# LinTempCont_4ch_proto.net
KiCad netlist of a schematic drawn in EAGLE
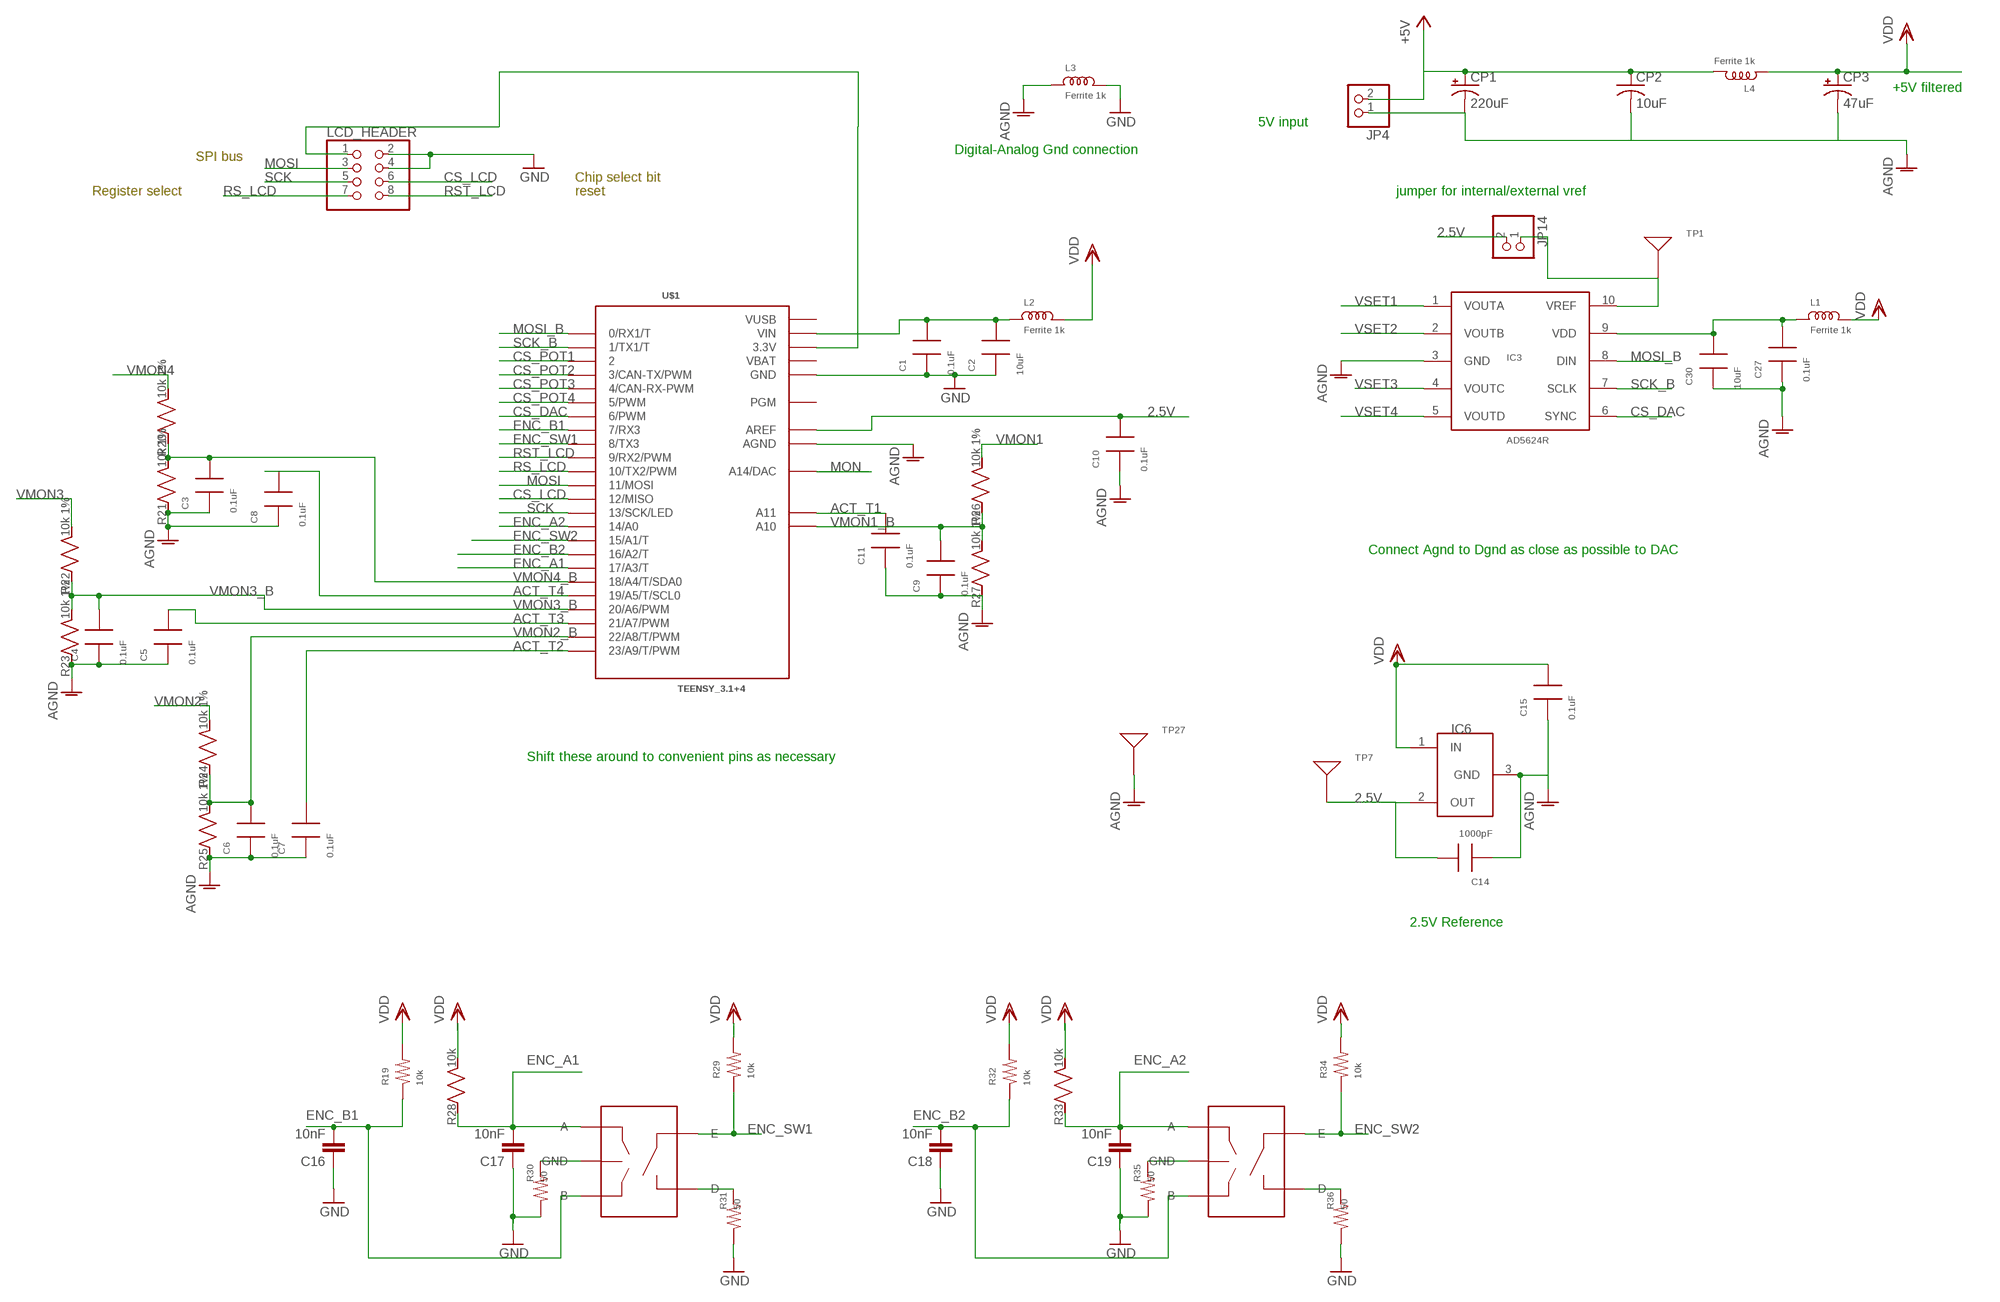
[diagram p0: schematic, sheet 1]
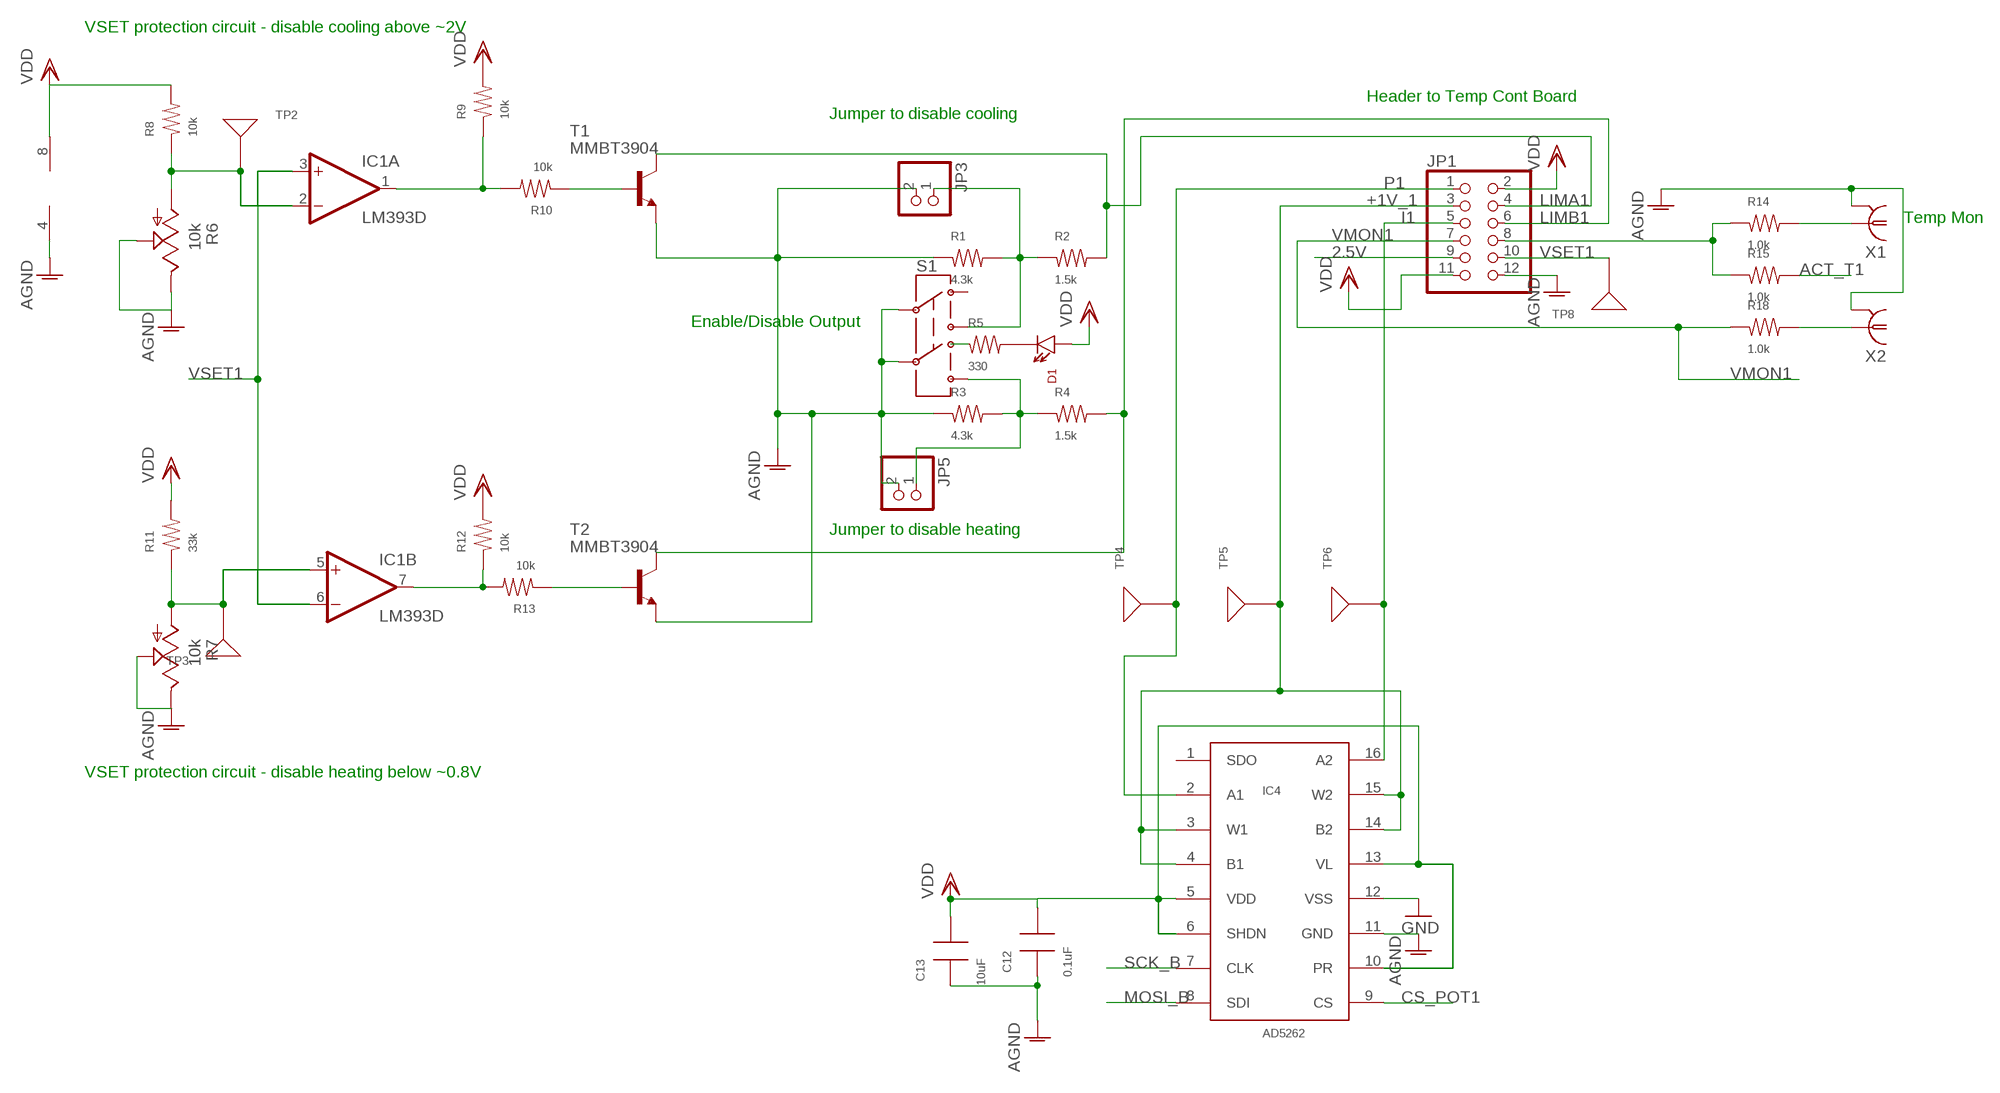
[diagram p1: schematic, sheet 2]
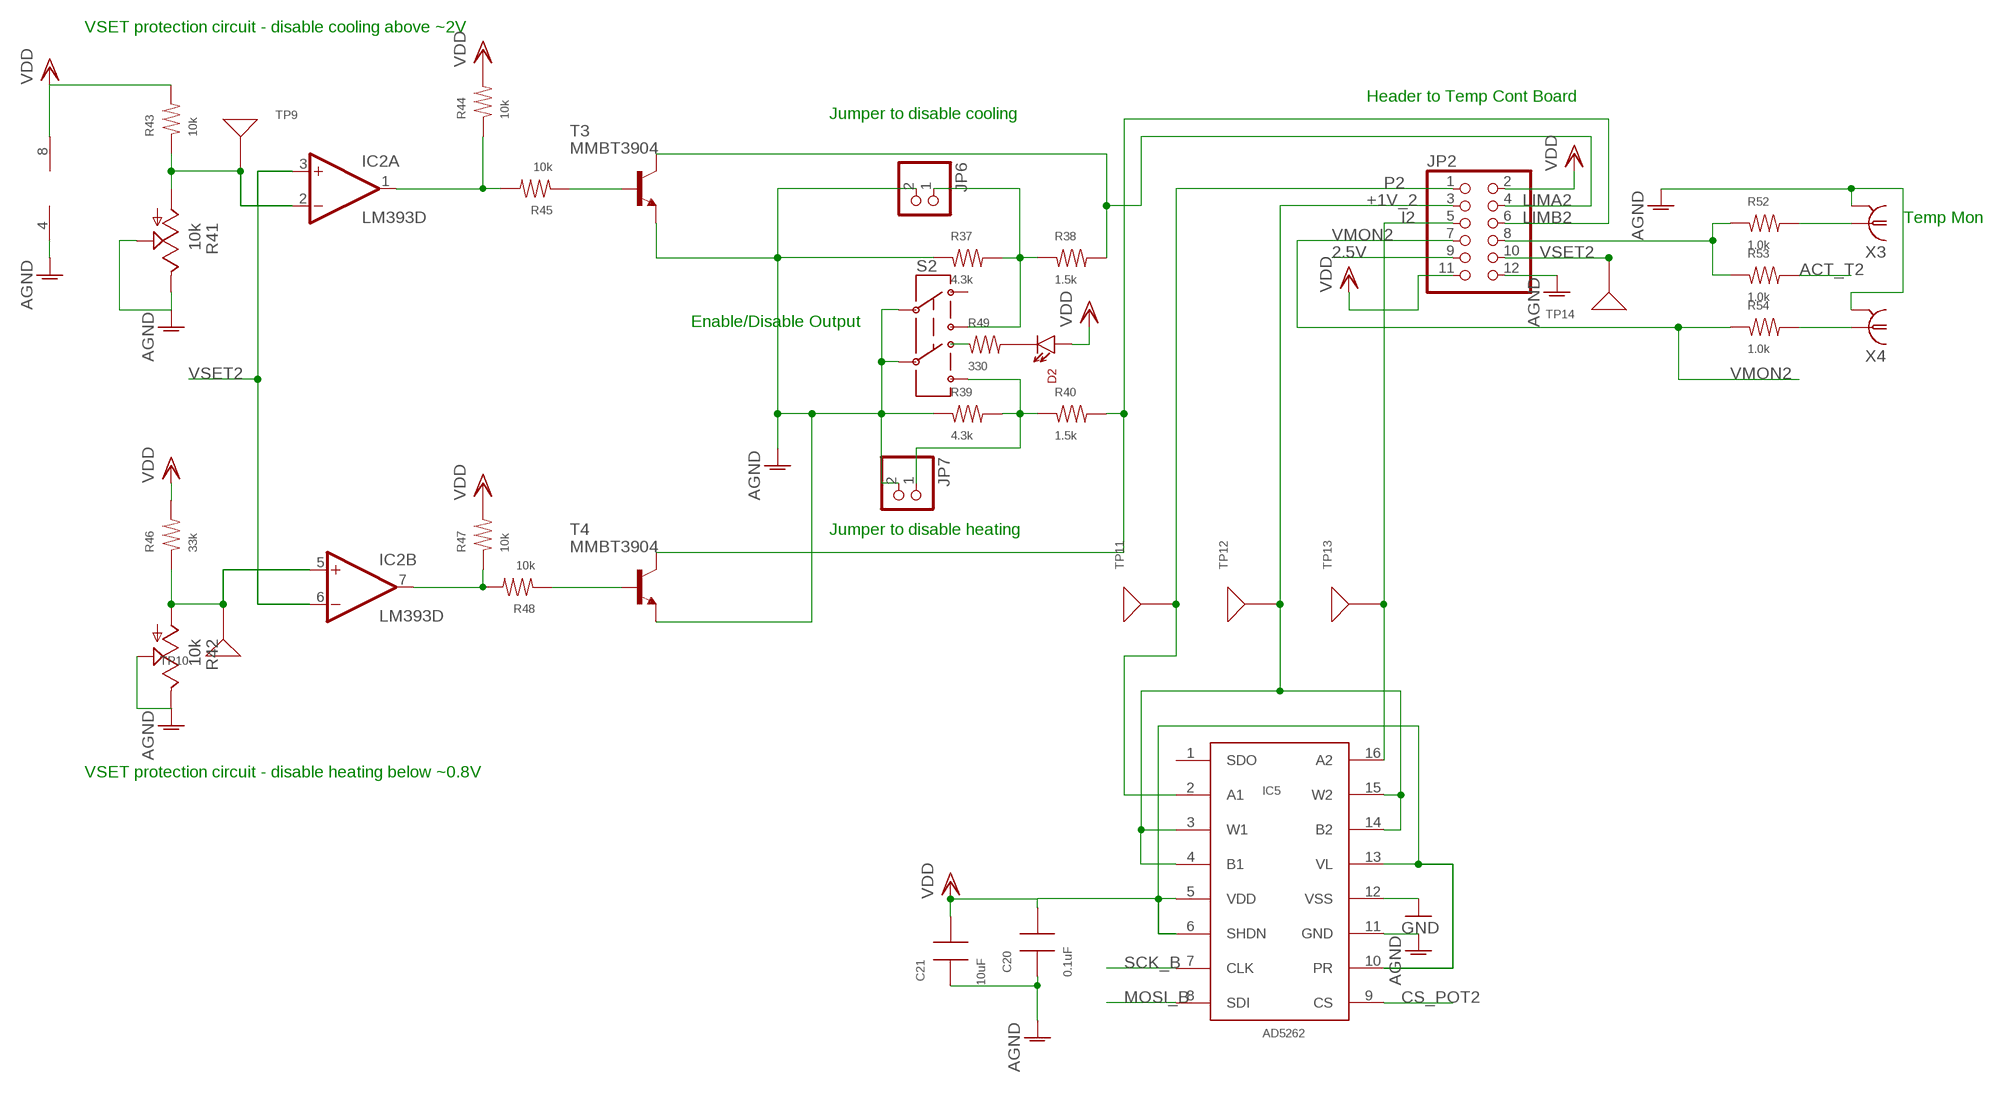
[diagram p2: schematic, sheet 3]
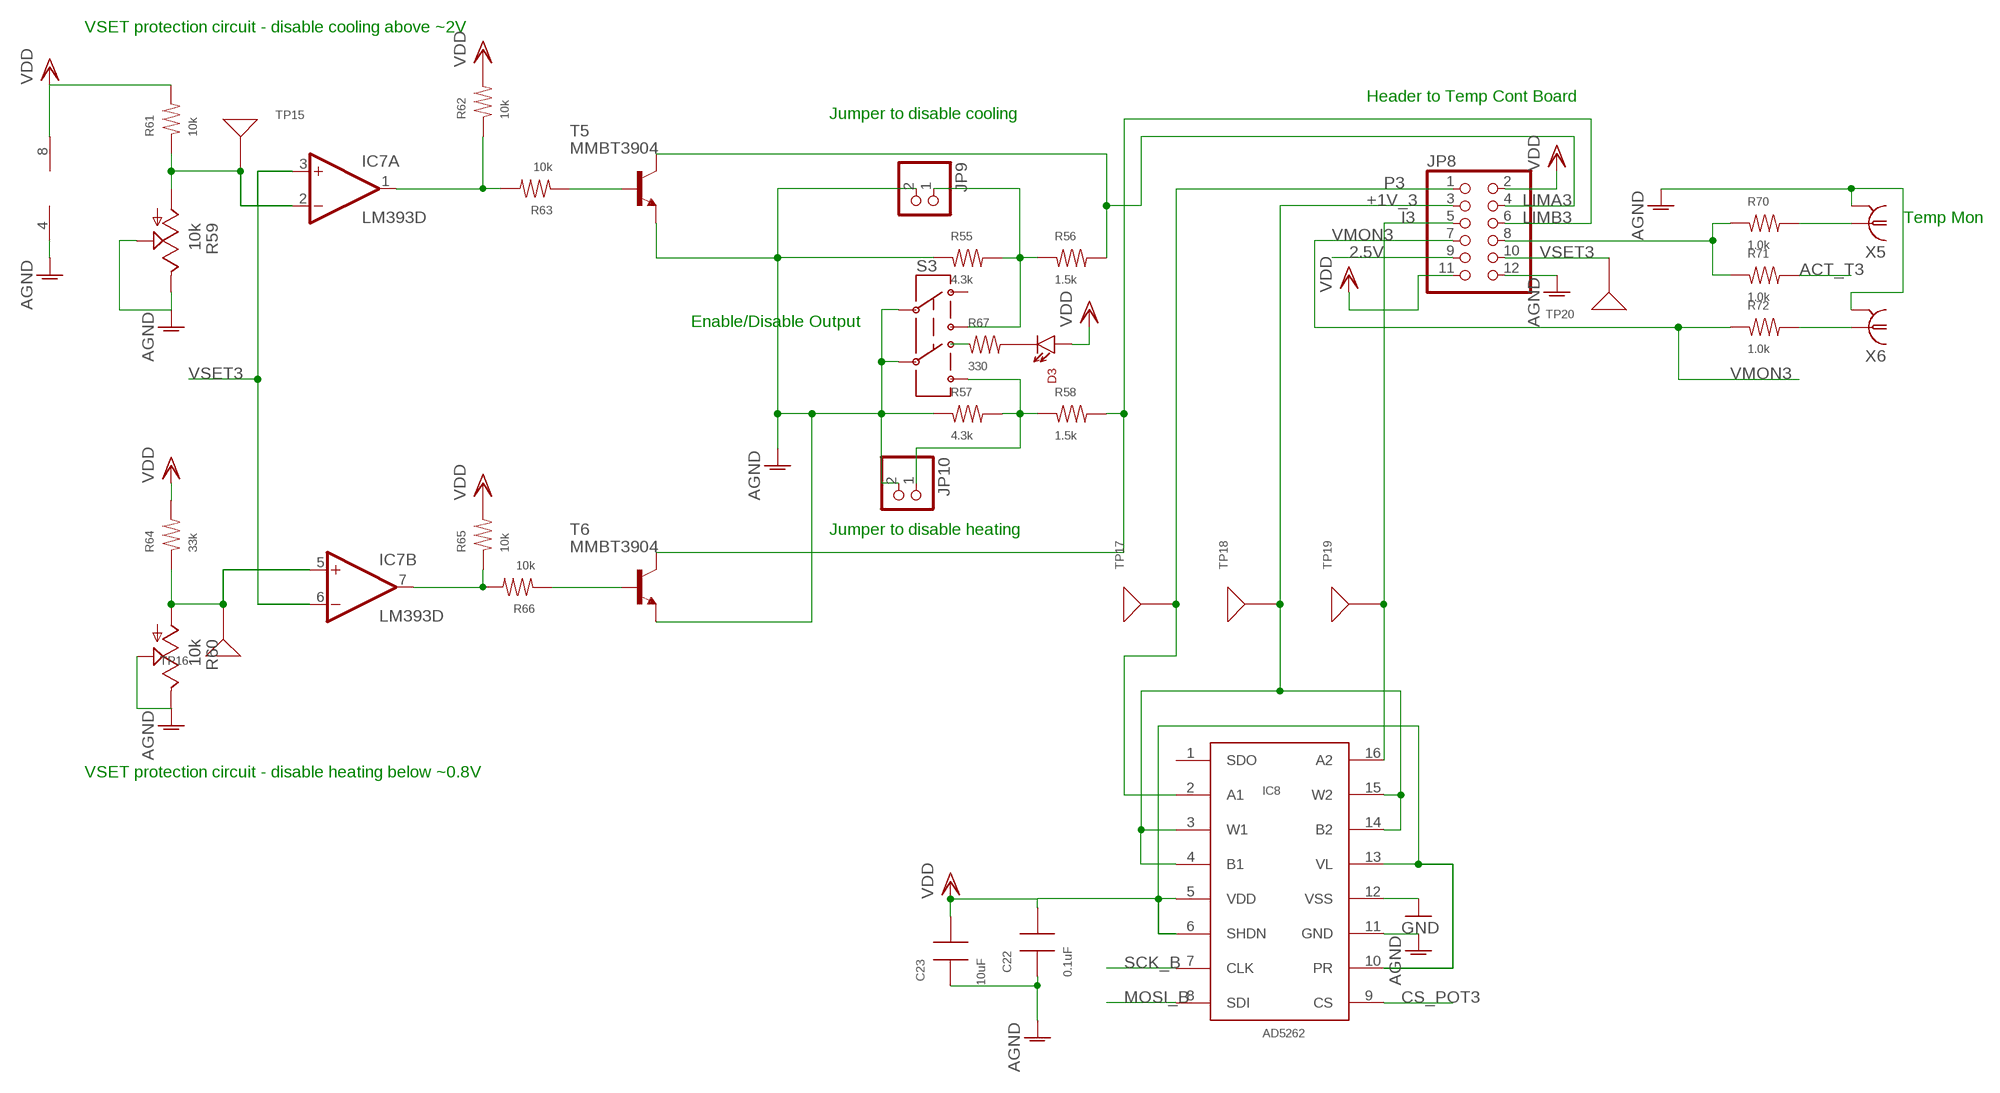
[diagram p3: schematic, sheet 4]
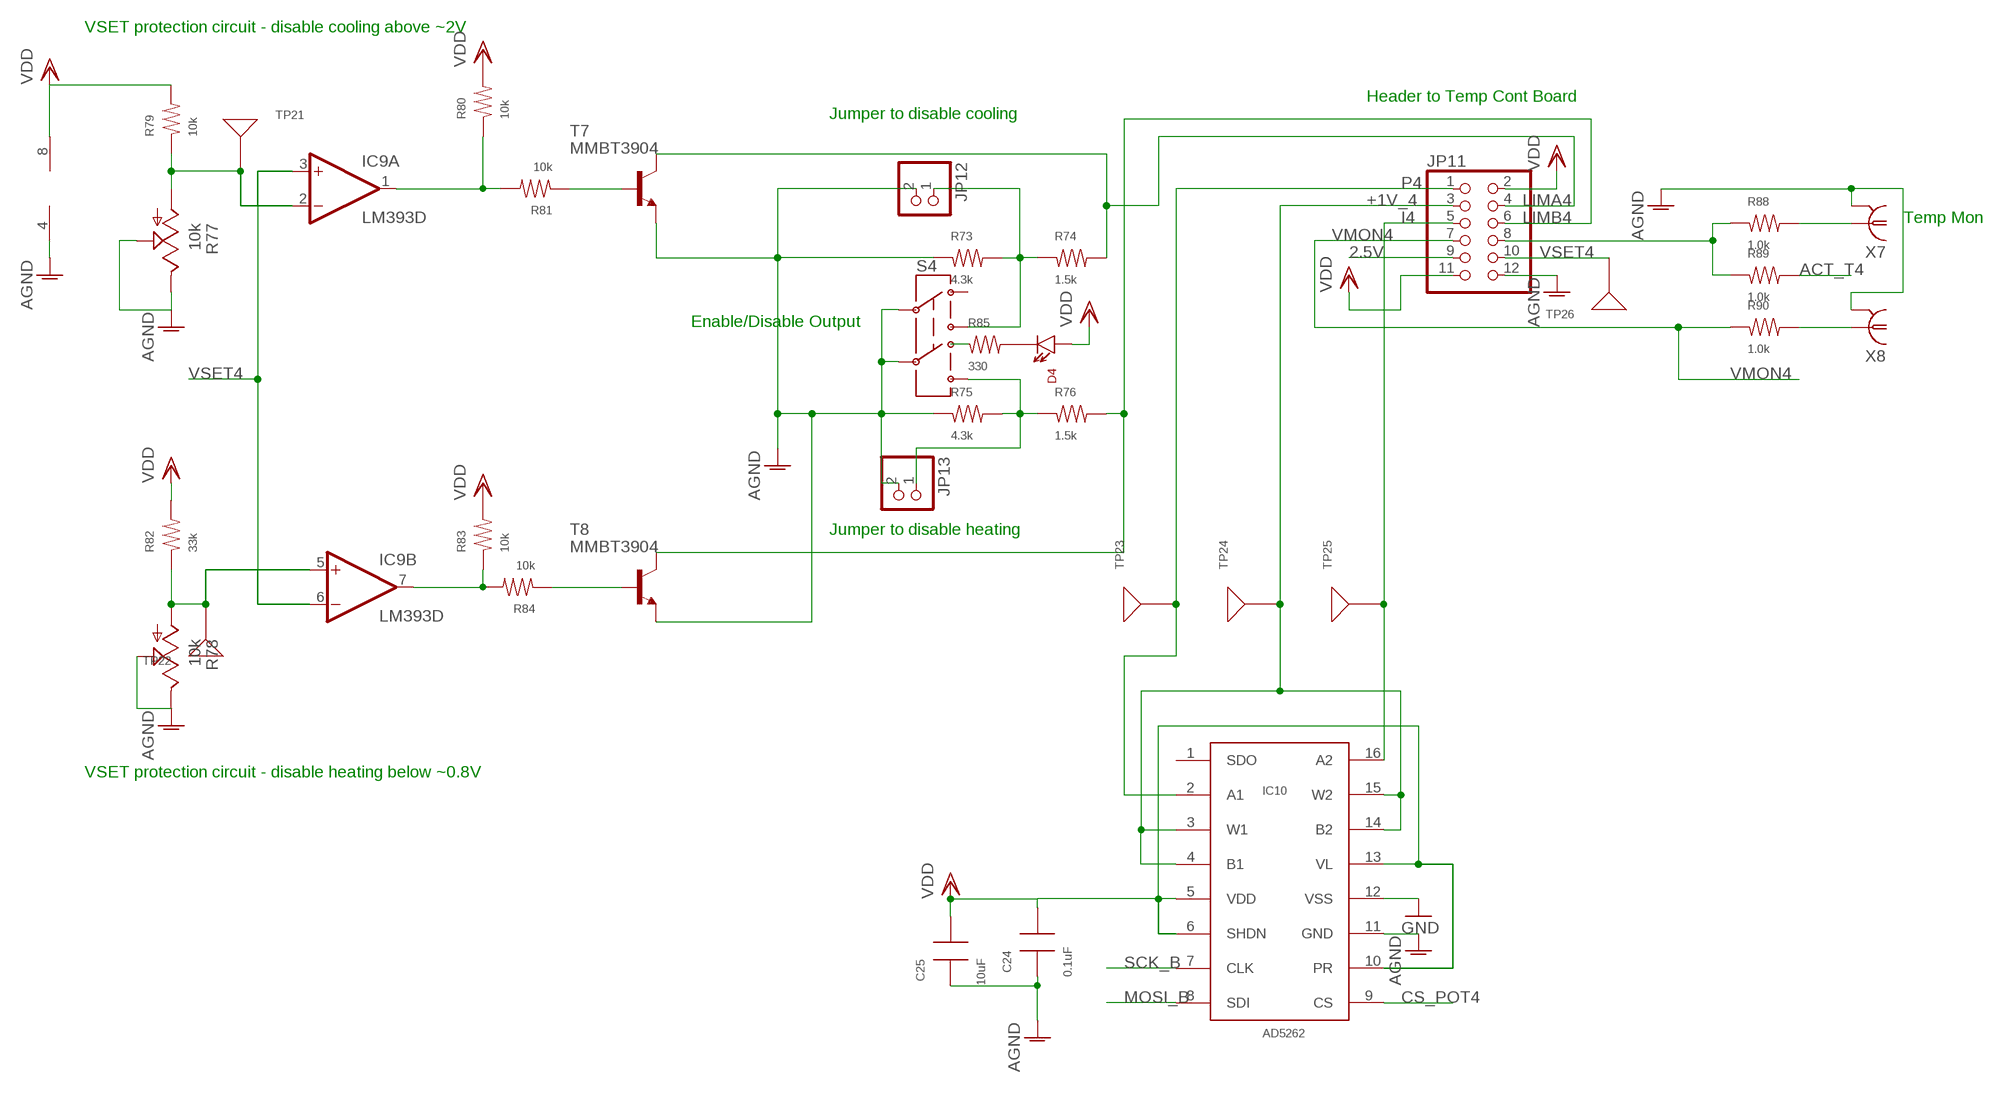
[diagram p4: schematic, sheet 5]

(export (version "E")
  (design (tool "Eeschema 10.0.6"))
  (components
    (comp (ref "C24")
      (value "0.1uF")
      (footprint "eagle-import:0603")
      (libsource (lib "eagle-import") (part "CAP0603"))
    )
    (comp (ref "C25")
      (value "10uF")
      (footprint "eagle-import:0805")
      (libsource (lib "eagle-import") (part "CAP0805"))
    )
    (comp (ref "D4")
      (value "LED/MINI-IND")
      (footprint "eagle-import:HLMP--F0010")
      (libsource (lib "eagle-import") (part "LED/MINI-IND"))
    )
    (comp (ref "IC9")
      (value "LM393D")
      (footprint "eagle-import:SO08")
      (libsource (lib "eagle-import") (part "LM393D"))
    )
    (comp (ref "IC10")
      (value "AD5262")
      (footprint "eagle-import:TSSOP16")
      (libsource (lib "eagle-import") (part "AD5262"))
    )
    (comp (ref "JP11")
      (value "PINHD-2X6/90")
      (footprint "eagle-import:2X06_90")
      (libsource (lib "eagle-import") (part "PINHD-2X6/90"))
    )
    (comp (ref "JP12")
      (value "PINHD-1X2")
      (footprint "eagle-import:1X02")
      (libsource (lib "eagle-import") (part "PINHD-1X2"))
    )
    (comp (ref "JP13")
      (value "PINHD-1X2")
      (footprint "eagle-import:1X02")
      (libsource (lib "eagle-import") (part "PINHD-1X2"))
    )
    (comp (ref "R73")
      (value "4.3k")
      (footprint "eagle-import:0603")
      (libsource (lib "eagle-import") (part "RES0603"))
    )
    (comp (ref "R74")
      (value "1.5k")
      (footprint "eagle-import:0603")
      (libsource (lib "eagle-import") (part "RES0603"))
    )
    (comp (ref "R75")
      (value "4.3k")
      (footprint "eagle-import:0603")
      (libsource (lib "eagle-import") (part "RES0603"))
    )
    (comp (ref "R76")
      (value "1.5k")
      (footprint "eagle-import:0603")
      (libsource (lib "eagle-import") (part "RES0603"))
    )
    (comp (ref "R77")
      (value "10k")
      (footprint "eagle-import:64WPOT")
      (libsource (lib "eagle-import") (part "MODEL64_TRIMPOT/TOP-ADJ"))
    )
    (comp (ref "R78")
      (value "10k")
      (footprint "eagle-import:64WPOT")
      (libsource (lib "eagle-import") (part "MODEL64_TRIMPOT/TOP-ADJ"))
    )
    (comp (ref "R79")
      (value "10k")
      (footprint "eagle-import:0603")
      (libsource (lib "eagle-import") (part "RES0603"))
    )
    (comp (ref "R80")
      (value "10k")
      (footprint "eagle-import:0603")
      (libsource (lib "eagle-import") (part "RES0603"))
    )
    (comp (ref "R81")
      (value "10k")
      (footprint "eagle-import:0603")
      (libsource (lib "eagle-import") (part "RES0603"))
    )
    (comp (ref "R82")
      (value "33k")
      (footprint "eagle-import:0603")
      (libsource (lib "eagle-import") (part "RES0603"))
    )
    (comp (ref "R83")
      (value "10k")
      (footprint "eagle-import:0603")
      (libsource (lib "eagle-import") (part "RES0603"))
    )
    (comp (ref "R84")
      (value "10k")
      (footprint "eagle-import:0603")
      (libsource (lib "eagle-import") (part "RES0603"))
    )
    (comp (ref "R85")
      (value "330")
      (footprint "eagle-import:0603")
      (libsource (lib "eagle-import") (part "RES0603"))
    )
    (comp (ref "R88")
      (value "1.0k")
      (footprint "eagle-import:0603")
      (libsource (lib "eagle-import") (part "RES0603"))
    )
    (comp (ref "R89")
      (value "1.0k")
      (footprint "eagle-import:0603")
      (libsource (lib "eagle-import") (part "RES0603"))
    )
    (comp (ref "R90")
      (value "1.0k")
      (footprint "eagle-import:0603")
      (libsource (lib "eagle-import") (part "RES0603"))
    )
    (comp (ref "S4")
      (value "SWITCH-DPDT/VER")
      (footprint "eagle-import:E-SWITCH-100-M7")
      (libsource (lib "eagle-import") (part "SWITCH-DPDT/VER"))
    )
    (comp (ref "T7")
      (value "MMBT3904")
      (footprint "eagle-import:SOT-23")
      (libsource (lib "eagle-import") (part "MMBT3904"))
    )
    (comp (ref "T8")
      (value "MMBT3904")
      (footprint "eagle-import:SOT-23")
      (libsource (lib "eagle-import") (part "MMBT3904"))
    )
    (comp (ref "TP21")
      (value "TESTPT")
      (footprint "eagle-import:1206TESTPAD")
      (libsource (lib "eagle-import") (part "TESTPT"))
    )
    (comp (ref "TP22")
      (value "TESTPT")
      (footprint "eagle-import:1206TESTPAD")
      (libsource (lib "eagle-import") (part "TESTPT"))
    )
    (comp (ref "TP23")
      (value "TESTPT")
      (footprint "eagle-import:1206TESTPAD")
      (libsource (lib "eagle-import") (part "TESTPT"))
    )
    (comp (ref "TP24")
      (value "TESTPT")
      (footprint "eagle-import:1206TESTPAD")
      (libsource (lib "eagle-import") (part "TESTPT"))
    )
    (comp (ref "TP25")
      (value "TESTPT")
      (footprint "eagle-import:1206TESTPAD")
      (libsource (lib "eagle-import") (part "TESTPT"))
    )
    (comp (ref "TP26")
      (value "TESTPT")
      (footprint "eagle-import:1206TESTPAD")
      (libsource (lib "eagle-import") (part "TESTPT"))
    )
    (comp (ref "X7")
      (value "BNC-H")
      (footprint "eagle-import:BNC90")
      (libsource (lib "eagle-import") (part "BNC-H"))
    )
    (comp (ref "X8")
      (value "BNC-H")
      (footprint "eagle-import:BNC90")
      (libsource (lib "eagle-import") (part "BNC-H"))
    )
    (comp (ref "C20")
      (value "0.1uF")
      (footprint "eagle-import:0603")
      (libsource (lib "eagle-import") (part "CAP0603"))
    )
    (comp (ref "C21")
      (value "10uF")
      (footprint "eagle-import:0805")
      (libsource (lib "eagle-import") (part "CAP0805"))
    )
    (comp (ref "D2")
      (value "LED/MINI-IND")
      (footprint "eagle-import:HLMP--F0010")
      (libsource (lib "eagle-import") (part "LED/MINI-IND"))
    )
    (comp (ref "IC2")
      (value "LM393D")
      (footprint "eagle-import:SO08")
      (libsource (lib "eagle-import") (part "LM393D"))
    )
    (comp (ref "IC5")
      (value "AD5262")
      (footprint "eagle-import:TSSOP16")
      (libsource (lib "eagle-import") (part "AD5262"))
    )
    (comp (ref "JP2")
      (value "PINHD-2X6/90")
      (footprint "eagle-import:2X06_90")
      (libsource (lib "eagle-import") (part "PINHD-2X6/90"))
    )
    (comp (ref "JP6")
      (value "PINHD-1X2")
      (footprint "eagle-import:1X02")
      (libsource (lib "eagle-import") (part "PINHD-1X2"))
    )
    (comp (ref "JP7")
      (value "PINHD-1X2")
      (footprint "eagle-import:1X02")
      (libsource (lib "eagle-import") (part "PINHD-1X2"))
    )
    (comp (ref "R37")
      (value "4.3k")
      (footprint "eagle-import:0603")
      (libsource (lib "eagle-import") (part "RES0603"))
    )
    (comp (ref "R38")
      (value "1.5k")
      (footprint "eagle-import:0603")
      (libsource (lib "eagle-import") (part "RES0603"))
    )
    (comp (ref "R39")
      (value "4.3k")
      (footprint "eagle-import:0603")
      (libsource (lib "eagle-import") (part "RES0603"))
    )
    (comp (ref "R40")
      (value "1.5k")
      (footprint "eagle-import:0603")
      (libsource (lib "eagle-import") (part "RES0603"))
    )
    (comp (ref "R41")
      (value "10k")
      (footprint "eagle-import:64WPOT")
      (libsource (lib "eagle-import") (part "MODEL64_TRIMPOT/TOP-ADJ"))
    )
    (comp (ref "R42")
      (value "10k")
      (footprint "eagle-import:64WPOT")
      (libsource (lib "eagle-import") (part "MODEL64_TRIMPOT/TOP-ADJ"))
    )
    (comp (ref "R43")
      (value "10k")
      (footprint "eagle-import:0603")
      (libsource (lib "eagle-import") (part "RES0603"))
    )
    (comp (ref "R44")
      (value "10k")
      (footprint "eagle-import:0603")
      (libsource (lib "eagle-import") (part "RES0603"))
    )
    (comp (ref "R45")
      (value "10k")
      (footprint "eagle-import:0603")
      (libsource (lib "eagle-import") (part "RES0603"))
    )
    (comp (ref "R46")
      (value "33k")
      (footprint "eagle-import:0603")
      (libsource (lib "eagle-import") (part "RES0603"))
    )
    (comp (ref "R47")
      (value "10k")
      (footprint "eagle-import:0603")
      (libsource (lib "eagle-import") (part "RES0603"))
    )
    (comp (ref "R48")
      (value "10k")
      (footprint "eagle-import:0603")
      (libsource (lib "eagle-import") (part "RES0603"))
    )
    (comp (ref "R49")
      (value "330")
      (footprint "eagle-import:0603")
      (libsource (lib "eagle-import") (part "RES0603"))
    )
    (comp (ref "R52")
      (value "1.0k")
      (footprint "eagle-import:0603")
      (libsource (lib "eagle-import") (part "RES0603"))
    )
    (comp (ref "R53")
      (value "1.0k")
      (footprint "eagle-import:0603")
      (libsource (lib "eagle-import") (part "RES0603"))
    )
    (comp (ref "R54")
      (value "1.0k")
      (footprint "eagle-import:0603")
      (libsource (lib "eagle-import") (part "RES0603"))
    )
    (comp (ref "S2")
      (value "SWITCH-DPDT/VER")
      (footprint "eagle-import:E-SWITCH-100-M7")
      (libsource (lib "eagle-import") (part "SWITCH-DPDT/VER"))
    )
    (comp (ref "T3")
      (value "MMBT3904")
      (footprint "eagle-import:SOT-23")
      (libsource (lib "eagle-import") (part "MMBT3904"))
    )
    (comp (ref "T4")
      (value "MMBT3904")
      (footprint "eagle-import:SOT-23")
      (libsource (lib "eagle-import") (part "MMBT3904"))
    )
    (comp (ref "TP9")
      (value "TESTPT")
      (footprint "eagle-import:1206TESTPAD")
      (libsource (lib "eagle-import") (part "TESTPT"))
    )
    (comp (ref "TP10")
      (value "TESTPT")
      (footprint "eagle-import:1206TESTPAD")
      (libsource (lib "eagle-import") (part "TESTPT"))
    )
    (comp (ref "TP11")
      (value "TESTPT")
      (footprint "eagle-import:1206TESTPAD")
      (libsource (lib "eagle-import") (part "TESTPT"))
    )
    (comp (ref "TP12")
      (value "TESTPT")
      (footprint "eagle-import:1206TESTPAD")
      (libsource (lib "eagle-import") (part "TESTPT"))
    )
    (comp (ref "TP13")
      (value "TESTPT")
      (footprint "eagle-import:1206TESTPAD")
      (libsource (lib "eagle-import") (part "TESTPT"))
    )
    (comp (ref "TP14")
      (value "TESTPT")
      (footprint "eagle-import:1206TESTPAD")
      (libsource (lib "eagle-import") (part "TESTPT"))
    )
    (comp (ref "X3")
      (value "BNC-H")
      (footprint "eagle-import:BNC90")
      (libsource (lib "eagle-import") (part "BNC-H"))
    )
    (comp (ref "X4")
      (value "BNC-H")
      (footprint "eagle-import:BNC90")
      (libsource (lib "eagle-import") (part "BNC-H"))
    )
    (comp (ref "C12")
      (value "0.1uF")
      (footprint "eagle-import:0603")
      (libsource (lib "eagle-import") (part "CAP0603"))
    )
    (comp (ref "C13")
      (value "10uF")
      (footprint "eagle-import:0805")
      (libsource (lib "eagle-import") (part "CAP0805"))
    )
    (comp (ref "D1")
      (value "LED/MINI-IND")
      (footprint "eagle-import:HLMP--F0010")
      (libsource (lib "eagle-import") (part "LED/MINI-IND"))
    )
    (comp (ref "IC1")
      (value "LM393D")
      (footprint "eagle-import:SO08")
      (libsource (lib "eagle-import") (part "LM393D"))
    )
    (comp (ref "IC4")
      (value "AD5262")
      (footprint "eagle-import:TSSOP16")
      (libsource (lib "eagle-import") (part "AD5262"))
    )
    (comp (ref "JP1")
      (value "PINHD-2X6/90")
      (footprint "eagle-import:2X06_90")
      (libsource (lib "eagle-import") (part "PINHD-2X6/90"))
    )
    (comp (ref "JP3")
      (value "PINHD-1X2")
      (footprint "eagle-import:1X02")
      (libsource (lib "eagle-import") (part "PINHD-1X2"))
    )
    (comp (ref "JP5")
      (value "PINHD-1X2")
      (footprint "eagle-import:1X02")
      (libsource (lib "eagle-import") (part "PINHD-1X2"))
    )
    (comp (ref "R1")
      (value "4.3k")
      (footprint "eagle-import:0603")
      (libsource (lib "eagle-import") (part "RES0603"))
    )
    (comp (ref "R2")
      (value "1.5k")
      (footprint "eagle-import:0603")
      (libsource (lib "eagle-import") (part "RES0603"))
    )
    (comp (ref "R3")
      (value "4.3k")
      (footprint "eagle-import:0603")
      (libsource (lib "eagle-import") (part "RES0603"))
    )
    (comp (ref "R4")
      (value "1.5k")
      (footprint "eagle-import:0603")
      (libsource (lib "eagle-import") (part "RES0603"))
    )
    (comp (ref "R5")
      (value "330")
      (footprint "eagle-import:0603")
      (libsource (lib "eagle-import") (part "RES0603"))
    )
    (comp (ref "R6")
      (value "10k")
      (footprint "eagle-import:64WPOT")
      (libsource (lib "eagle-import") (part "MODEL64_TRIMPOT/TOP-ADJ"))
    )
    (comp (ref "R7")
      (value "10k")
      (footprint "eagle-import:64WPOT")
      (libsource (lib "eagle-import") (part "MODEL64_TRIMPOT/TOP-ADJ"))
    )
    (comp (ref "R8")
      (value "10k")
      (footprint "eagle-import:0603")
      (libsource (lib "eagle-import") (part "RES0603"))
    )
    (comp (ref "R9")
      (value "10k")
      (footprint "eagle-import:0603")
      (libsource (lib "eagle-import") (part "RES0603"))
    )
    (comp (ref "R10")
      (value "10k")
      (footprint "eagle-import:0603")
      (libsource (lib "eagle-import") (part "RES0603"))
    )
    (comp (ref "R11")
      (value "33k")
      (footprint "eagle-import:0603")
      (libsource (lib "eagle-import") (part "RES0603"))
    )
    (comp (ref "R12")
      (value "10k")
      (footprint "eagle-import:0603")
      (libsource (lib "eagle-import") (part "RES0603"))
    )
    (comp (ref "R13")
      (value "10k")
      (footprint "eagle-import:0603")
      (libsource (lib "eagle-import") (part "RES0603"))
    )
    (comp (ref "R14")
      (value "1.0k")
      (footprint "eagle-import:0603")
      (libsource (lib "eagle-import") (part "RES0603"))
    )
    (comp (ref "R15")
      (value "1.0k")
      (footprint "eagle-import:0603")
      (libsource (lib "eagle-import") (part "RES0603"))
    )
    (comp (ref "R18")
      (value "1.0k")
      (footprint "eagle-import:0603")
      (libsource (lib "eagle-import") (part "RES0603"))
    )
    (comp (ref "S1")
      (value "SWITCH-DPDT/VER")
      (footprint "eagle-import:E-SWITCH-100-M7")
      (libsource (lib "eagle-import") (part "SWITCH-DPDT/VER"))
    )
    (comp (ref "T1")
      (value "MMBT3904")
      (footprint "eagle-import:SOT-23")
      (libsource (lib "eagle-import") (part "MMBT3904"))
    )
    (comp (ref "T2")
      (value "MMBT3904")
      (footprint "eagle-import:SOT-23")
      (libsource (lib "eagle-import") (part "MMBT3904"))
    )
    (comp (ref "TP2")
      (value "TESTPT")
      (footprint "eagle-import:1206TESTPAD")
      (libsource (lib "eagle-import") (part "TESTPT"))
    )
    (comp (ref "TP3")
      (value "TESTPT")
      (footprint "eagle-import:1206TESTPAD")
      (libsource (lib "eagle-import") (part "TESTPT"))
    )
    (comp (ref "TP4")
      (value "TESTPT")
      (footprint "eagle-import:1206TESTPAD")
      (libsource (lib "eagle-import") (part "TESTPT"))
    )
    (comp (ref "TP5")
      (value "TESTPT")
      (footprint "eagle-import:1206TESTPAD")
      (libsource (lib "eagle-import") (part "TESTPT"))
    )
    (comp (ref "TP6")
      (value "TESTPT")
      (footprint "eagle-import:1206TESTPAD")
      (libsource (lib "eagle-import") (part "TESTPT"))
    )
    (comp (ref "TP8")
      (value "TESTPT")
      (footprint "eagle-import:1206TESTPAD")
      (libsource (lib "eagle-import") (part "TESTPT"))
    )
    (comp (ref "X1")
      (value "BNC-H")
      (footprint "eagle-import:BNC90")
      (libsource (lib "eagle-import") (part "BNC-H"))
    )
    (comp (ref "X2")
      (value "BNC-H")
      (footprint "eagle-import:BNC90")
      (libsource (lib "eagle-import") (part "BNC-H"))
    )
    (comp (ref "C1")
      (value "0.1uF")
      (footprint "eagle-import:0603")
      (libsource (lib "eagle-import") (part "CAP0603"))
    )
    (comp (ref "C2")
      (value "10uF")
      (footprint "eagle-import:0805")
      (libsource (lib "eagle-import") (part "CAP0805"))
    )
    (comp (ref "C3")
      (value "0.1uF")
      (footprint "eagle-import:0603")
      (libsource (lib "eagle-import") (part "CAP0603"))
    )
    (comp (ref "C4")
      (value "0.1uF")
      (footprint "eagle-import:0603")
      (libsource (lib "eagle-import") (part "CAP0603"))
    )
    (comp (ref "C5")
      (value "0.1uF")
      (footprint "eagle-import:0603")
      (libsource (lib "eagle-import") (part "CAP0603"))
    )
    (comp (ref "C6")
      (value "0.1uF")
      (footprint "eagle-import:0603")
      (libsource (lib "eagle-import") (part "CAP0603"))
    )
    (comp (ref "C7")
      (value "0.1uF")
      (footprint "eagle-import:0603")
      (libsource (lib "eagle-import") (part "CAP0603"))
    )
    (comp (ref "C8")
      (value "0.1uF")
      (footprint "eagle-import:0603")
      (libsource (lib "eagle-import") (part "CAP0603"))
    )
    (comp (ref "C9")
      (value "0.1uF")
      (footprint "eagle-import:0603")
      (libsource (lib "eagle-import") (part "CAP0603"))
    )
    (comp (ref "C10")
      (value "0.1uF")
      (footprint "eagle-import:0603")
      (libsource (lib "eagle-import") (part "CAP0603"))
    )
    (comp (ref "C11")
      (value "0.1uF")
      (footprint "eagle-import:0603")
      (libsource (lib "eagle-import") (part "CAP0603"))
    )
    (comp (ref "C14")
      (value "1000pF")
      (footprint "eagle-import:0603")
      (libsource (lib "eagle-import") (part "CAP0603"))
    )
    (comp (ref "C15")
      (value "0.1uF")
      (footprint "eagle-import:0603")
      (libsource (lib "eagle-import") (part "CAP0603"))
    )
    (comp (ref "C16")
      (value "10nF")
      (footprint "eagle-import:C0603")
      (libsource (lib "eagle-import") (part "C-EUC0603"))
    )
    (comp (ref "C17")
      (value "10nF")
      (footprint "eagle-import:C0603")
      (libsource (lib "eagle-import") (part "C-EUC0603"))
    )
    (comp (ref "C18")
      (value "10nF")
      (footprint "eagle-import:C0603")
      (libsource (lib "eagle-import") (part "C-EUC0603"))
    )
    (comp (ref "C19")
      (value "10nF")
      (footprint "eagle-import:C0603")
      (libsource (lib "eagle-import") (part "C-EUC0603"))
    )
    (comp (ref "C27")
      (value "0.1uF")
      (footprint "eagle-import:0603")
      (libsource (lib "eagle-import") (part "CAP0603"))
    )
    (comp (ref "C30")
      (value "10uF")
      (footprint "eagle-import:0805")
      (libsource (lib "eagle-import") (part "CAP0805"))
    )
    (comp (ref "CP1")
      (value "220uF")
      (footprint "eagle-import:PANASONIC_F")
      (libsource (lib "eagle-import") (part "CPOL-USF"))
    )
    (comp (ref "CP2")
      (value "10uF")
      (footprint "eagle-import:C0805K")
      (libsource (lib "eagle-import") (part "C-USC0805K"))
    )
    (comp (ref "CP3")
      (value "47uF")
      (footprint "eagle-import:CT7343")
      (libsource (lib "eagle-import") (part "CPOL-USCT7343"))
    )
    (comp (ref "ENC1")
      (value "PEC09")
      (footprint "eagle-import:PEC092320FS")
      (libsource (lib "eagle-import") (part "PEC09"))
    )
    (comp (ref "ENC2")
      (value "PEC09")
      (footprint "eagle-import:PEC092320FS")
      (libsource (lib "eagle-import") (part "PEC09"))
    )
    (comp (ref "IC3")
      (value "AD5624R")
      (footprint "eagle-import:MSOP10")
      (libsource (lib "eagle-import") (part "AD5624R"))
    )
    (comp (ref "IC6")
      (value "TS6001")
      (footprint "eagle-import:SOT-23")
      (libsource (lib "eagle-import") (part "TS6001"))
    )
    (comp (ref "JP4")
      (value "SCRWTRM-1X2")
      (footprint "eagle-import:1X02_SCRWTRM")
      (libsource (lib "eagle-import") (part "SCRWTRM-1X2"))
    )
    (comp (ref "JP14")
      (value "PINHD-1X2")
      (footprint "eagle-import:1X02")
      (libsource (lib "eagle-import") (part "PINHD-1X2"))
    )
    (comp (ref "L1")
      (value "Ferrite 1k")
      (footprint "eagle-import:0805")
      (libsource (lib "eagle-import") (part "INDUCTOR-0805"))
    )
    (comp (ref "L2")
      (value "Ferrite 1k")
      (footprint "eagle-import:0805")
      (libsource (lib "eagle-import") (part "INDUCTOR-0805"))
    )
    (comp (ref "L3")
      (value "Ferrite 1k")
      (footprint "eagle-import:0805")
      (libsource (lib "eagle-import") (part "INDUCTOR-0805"))
    )
    (comp (ref "L4")
      (value "Ferrite 1k")
      (footprint "eagle-import:0805")
      (libsource (lib "eagle-import") (part "INDUCTOR-0805"))
    )
    (comp (ref "LCD_HEADER")
      (value "PINHD-2X4-SHROUD")
      (footprint "eagle-import:ML08")
      (libsource (lib "eagle-import") (part "PINHD-2X4-SHROUD"))
    )
    (comp (ref "R19")
      (value "10k")
      (footprint "eagle-import:0603")
      (libsource (lib "eagle-import") (part "RES0603"))
    )
    (comp (ref "R20")
      (value "10k 1%")
      (footprint "eagle-import:R_0603")
      (libsource (lib "eagle-import") (part "R_SMDR0603"))
    )
    (comp (ref "R21")
      (value "10k 1%")
      (footprint "eagle-import:R_0603")
      (libsource (lib "eagle-import") (part "R_SMDR0603"))
    )
    (comp (ref "R22")
      (value "10k 1%")
      (footprint "eagle-import:R_0603")
      (libsource (lib "eagle-import") (part "R_SMDR0603"))
    )
    (comp (ref "R23")
      (value "10k 1%")
      (footprint "eagle-import:R_0603")
      (libsource (lib "eagle-import") (part "R_SMDR0603"))
    )
    (comp (ref "R24")
      (value "10k 1%")
      (footprint "eagle-import:R_0603")
      (libsource (lib "eagle-import") (part "R_SMDR0603"))
    )
    (comp (ref "R25")
      (value "10k 1%")
      (footprint "eagle-import:R_0603")
      (libsource (lib "eagle-import") (part "R_SMDR0603"))
    )
    (comp (ref "R26")
      (value "10k 1%")
      (footprint "eagle-import:R_0603")
      (libsource (lib "eagle-import") (part "R_SMDR0603"))
    )
    (comp (ref "R27")
      (value "10k 1%")
      (footprint "eagle-import:R_0603")
      (libsource (lib "eagle-import") (part "R_SMDR0603"))
    )
    (comp (ref "R28")
      (value "10k")
      (footprint "eagle-import:R_0603")
      (libsource (lib "eagle-import") (part "R_SMDR0603"))
    )
    (comp (ref "R29")
      (value "10k")
      (footprint "eagle-import:0603")
      (libsource (lib "eagle-import") (part "RES0603"))
    )
    (comp (ref "R30")
      (value "50")
      (footprint "eagle-import:0603")
      (libsource (lib "eagle-import") (part "RES0603"))
    )
    (comp (ref "R31")
      (value "50")
      (footprint "eagle-import:0603")
      (libsource (lib "eagle-import") (part "RES0603"))
    )
    (comp (ref "R32")
      (value "10k")
      (footprint "eagle-import:0603")
      (libsource (lib "eagle-import") (part "RES0603"))
    )
    (comp (ref "R33")
      (value "10k")
      (footprint "eagle-import:R_0603")
      (libsource (lib "eagle-import") (part "R_SMDR0603"))
    )
    (comp (ref "R34")
      (value "10k")
      (footprint "eagle-import:0603")
      (libsource (lib "eagle-import") (part "RES0603"))
    )
    (comp (ref "R35")
      (value "50")
      (footprint "eagle-import:0603")
      (libsource (lib "eagle-import") (part "RES0603"))
    )
    (comp (ref "R36")
      (value "50")
      (footprint "eagle-import:0603")
      (libsource (lib "eagle-import") (part "RES0603"))
    )
    (comp (ref "TP1")
      (value "TESTPT")
      (footprint "eagle-import:1206TESTPAD")
      (libsource (lib "eagle-import") (part "TESTPT"))
    )
    (comp (ref "TP7")
      (value "TESTPT")
      (footprint "eagle-import:1206TESTPAD")
      (libsource (lib "eagle-import") (part "TESTPT"))
    )
    (comp (ref "TP27")
      (value "TESTPT")
      (footprint "eagle-import:1206TESTPAD")
      (libsource (lib "eagle-import") (part "TESTPT"))
    )
    (comp (ref "U$1")
      (value "TEENSY_3.1+4")
      (footprint "eagle-import:TEENSY_3.1+4")
      (libsource (lib "eagle-import") (part "TEENSY_3.1+4"))
    )
    (comp (ref "C22")
      (value "0.1uF")
      (footprint "eagle-import:0603")
      (libsource (lib "eagle-import") (part "CAP0603"))
    )
    (comp (ref "C23")
      (value "10uF")
      (footprint "eagle-import:0805")
      (libsource (lib "eagle-import") (part "CAP0805"))
    )
    (comp (ref "D3")
      (value "LED/MINI-IND")
      (footprint "eagle-import:HLMP--F0010")
      (libsource (lib "eagle-import") (part "LED/MINI-IND"))
    )
    (comp (ref "IC7")
      (value "LM393D")
      (footprint "eagle-import:SO08")
      (libsource (lib "eagle-import") (part "LM393D"))
    )
    (comp (ref "IC8")
      (value "AD5262")
      (footprint "eagle-import:TSSOP16")
      (libsource (lib "eagle-import") (part "AD5262"))
    )
    (comp (ref "JP8")
      (value "PINHD-2X6/90")
      (footprint "eagle-import:2X06_90")
      (libsource (lib "eagle-import") (part "PINHD-2X6/90"))
    )
    (comp (ref "JP9")
      (value "PINHD-1X2")
      (footprint "eagle-import:1X02")
      (libsource (lib "eagle-import") (part "PINHD-1X2"))
    )
    (comp (ref "JP10")
      (value "PINHD-1X2")
      (footprint "eagle-import:1X02")
      (libsource (lib "eagle-import") (part "PINHD-1X2"))
    )
    (comp (ref "R55")
      (value "4.3k")
      (footprint "eagle-import:0603")
      (libsource (lib "eagle-import") (part "RES0603"))
    )
    (comp (ref "R56")
      (value "1.5k")
      (footprint "eagle-import:0603")
      (libsource (lib "eagle-import") (part "RES0603"))
    )
    (comp (ref "R57")
      (value "4.3k")
      (footprint "eagle-import:0603")
      (libsource (lib "eagle-import") (part "RES0603"))
    )
    (comp (ref "R58")
      (value "1.5k")
      (footprint "eagle-import:0603")
      (libsource (lib "eagle-import") (part "RES0603"))
    )
    (comp (ref "R59")
      (value "10k")
      (footprint "eagle-import:64WPOT")
      (libsource (lib "eagle-import") (part "MODEL64_TRIMPOT/TOP-ADJ"))
    )
    (comp (ref "R60")
      (value "10k")
      (footprint "eagle-import:64WPOT")
      (libsource (lib "eagle-import") (part "MODEL64_TRIMPOT/TOP-ADJ"))
    )
    (comp (ref "R61")
      (value "10k")
      (footprint "eagle-import:0603")
      (libsource (lib "eagle-import") (part "RES0603"))
    )
    (comp (ref "R62")
      (value "10k")
      (footprint "eagle-import:0603")
      (libsource (lib "eagle-import") (part "RES0603"))
    )
    (comp (ref "R63")
      (value "10k")
      (footprint "eagle-import:0603")
      (libsource (lib "eagle-import") (part "RES0603"))
    )
    (comp (ref "R64")
      (value "33k")
      (footprint "eagle-import:0603")
      (libsource (lib "eagle-import") (part "RES0603"))
    )
    (comp (ref "R65")
      (value "10k")
      (footprint "eagle-import:0603")
      (libsource (lib "eagle-import") (part "RES0603"))
    )
    (comp (ref "R66")
      (value "10k")
      (footprint "eagle-import:0603")
      (libsource (lib "eagle-import") (part "RES0603"))
    )
    (comp (ref "R67")
      (value "330")
      (footprint "eagle-import:0603")
      (libsource (lib "eagle-import") (part "RES0603"))
    )
    (comp (ref "R70")
      (value "1.0k")
      (footprint "eagle-import:0603")
      (libsource (lib "eagle-import") (part "RES0603"))
    )
    (comp (ref "R71")
      (value "1.0k")
      (footprint "eagle-import:0603")
      (libsource (lib "eagle-import") (part "RES0603"))
    )
    (comp (ref "R72")
      (value "1.0k")
      (footprint "eagle-import:0603")
      (libsource (lib "eagle-import") (part "RES0603"))
    )
    (comp (ref "S3")
      (value "SWITCH-DPDT/VER")
      (footprint "eagle-import:E-SWITCH-100-M7")
      (libsource (lib "eagle-import") (part "SWITCH-DPDT/VER"))
    )
    (comp (ref "T5")
      (value "MMBT3904")
      (footprint "eagle-import:SOT-23")
      (libsource (lib "eagle-import") (part "MMBT3904"))
    )
    (comp (ref "T6")
      (value "MMBT3904")
      (footprint "eagle-import:SOT-23")
      (libsource (lib "eagle-import") (part "MMBT3904"))
    )
    (comp (ref "TP15")
      (value "TESTPT")
      (footprint "eagle-import:1206TESTPAD")
      (libsource (lib "eagle-import") (part "TESTPT"))
    )
    (comp (ref "TP16")
      (value "TESTPT")
      (footprint "eagle-import:1206TESTPAD")
      (libsource (lib "eagle-import") (part "TESTPT"))
    )
    (comp (ref "TP17")
      (value "TESTPT")
      (footprint "eagle-import:1206TESTPAD")
      (libsource (lib "eagle-import") (part "TESTPT"))
    )
    (comp (ref "TP18")
      (value "TESTPT")
      (footprint "eagle-import:1206TESTPAD")
      (libsource (lib "eagle-import") (part "TESTPT"))
    )
    (comp (ref "TP19")
      (value "TESTPT")
      (footprint "eagle-import:1206TESTPAD")
      (libsource (lib "eagle-import") (part "TESTPT"))
    )
    (comp (ref "TP20")
      (value "TESTPT")
      (footprint "eagle-import:1206TESTPAD")
      (libsource (lib "eagle-import") (part "TESTPT"))
    )
    (comp (ref "X5")
      (value "BNC-H")
      (footprint "eagle-import:BNC90")
      (libsource (lib "eagle-import") (part "BNC-H"))
    )
    (comp (ref "X6")
      (value "BNC-H")
      (footprint "eagle-import:BNC90")
      (libsource (lib "eagle-import") (part "BNC-H"))
    )
  )
  (nets
    (net (code "1") (name "+1V_1") (class "Default")
      (node (ref "IC4") (pin "14") (pinfunction "B2_14") (pintype "bidirectional"))
      (node (ref "IC4") (pin "15") (pinfunction "W2_15") (pintype "bidirectional"))
      (node (ref "IC4") (pin "3") (pinfunction "W1_3") (pintype "bidirectional"))
      (node (ref "IC4") (pin "4") (pinfunction "B1_4") (pintype "bidirectional"))
      (node (ref "JP1") (pin "3") (pinfunction "3_3") (pintype "passive"))
      (node (ref "TP5") (pin "P$1") (pinfunction "P$1_P$1") (pintype "bidirectional"))
    )
    (net (code "2") (name "+1V_2") (class "Default")
      (node (ref "IC5") (pin "14") (pinfunction "B2_14") (pintype "bidirectional"))
      (node (ref "IC5") (pin "15") (pinfunction "W2_15") (pintype "bidirectional"))
      (node (ref "IC5") (pin "3") (pinfunction "W1_3") (pintype "bidirectional"))
      (node (ref "IC5") (pin "4") (pinfunction "B1_4") (pintype "bidirectional"))
      (node (ref "JP2") (pin "3") (pinfunction "3_3") (pintype "passive"))
      (node (ref "TP12") (pin "P$1") (pinfunction "P$1_P$1") (pintype "bidirectional"))
    )
    (net (code "3") (name "+1V_3") (class "Default")
      (node (ref "IC8") (pin "14") (pinfunction "B2_14") (pintype "bidirectional"))
      (node (ref "IC8") (pin "15") (pinfunction "W2_15") (pintype "bidirectional"))
      (node (ref "IC8") (pin "3") (pinfunction "W1_3") (pintype "bidirectional"))
      (node (ref "IC8") (pin "4") (pinfunction "B1_4") (pintype "bidirectional"))
      (node (ref "JP8") (pin "3") (pinfunction "3_3") (pintype "passive"))
      (node (ref "TP18") (pin "P$1") (pinfunction "P$1_P$1") (pintype "bidirectional"))
    )
    (net (code "4") (name "+1V_4") (class "Default")
      (node (ref "IC10") (pin "14") (pinfunction "B2_14") (pintype "bidirectional"))
      (node (ref "IC10") (pin "15") (pinfunction "W2_15") (pintype "bidirectional"))
      (node (ref "IC10") (pin "3") (pinfunction "W1_3") (pintype "bidirectional"))
      (node (ref "IC10") (pin "4") (pinfunction "B1_4") (pintype "bidirectional"))
      (node (ref "JP11") (pin "3") (pinfunction "3_3") (pintype "passive"))
      (node (ref "TP24") (pin "P$1") (pinfunction "P$1_P$1") (pintype "bidirectional"))
    )
    (net (code "5") (name "+5V") (class "Default")
      (node (ref "CP1") (pin "+") (pinfunction "+_+") (pintype "passive"))
      (node (ref "CP2") (pin "1") (pinfunction "1_1") (pintype "passive"))
      (node (ref "JP4") (pin "2") (pinfunction "2_2") (pintype "passive"))
      (node (ref "L4") (pin "2") (pinfunction "P$2_2") (pintype "passive"))
    )
    (net (code "6") (name "2.5V") (class "Default")
      (node (ref "C10") (pin "2") (pinfunction "P$2_2") (pintype "passive"))
      (node (ref "C14") (pin "2") (pinfunction "P$2_2") (pintype "passive"))
      (node (ref "IC6") (pin "2") (pinfunction "OUT_2") (pintype "bidirectional"))
      (node (ref "JP1") (pin "9") (pinfunction "9_9") (pintype "passive"))
      (node (ref "JP11") (pin "9") (pinfunction "9_9") (pintype "passive"))
      (node (ref "JP14") (pin "2") (pinfunction "2_2") (pintype "passive"))
      (node (ref "JP2") (pin "9") (pinfunction "9_9") (pintype "passive"))
      (node (ref "JP8") (pin "9") (pinfunction "9_9") (pintype "passive"))
      (node (ref "TP7") (pin "P$1") (pinfunction "P$1_P$1") (pintype "bidirectional"))
      (node (ref "U$1") (pin "AREF") (pinfunction "AREF_AREF") (pintype "power_in"))
    )
    (net (code "7") (name "ACT_T1") (class "Default")
      (node (ref "C11") (pin "2") (pinfunction "P$2_2") (pintype "passive"))
      (node (ref "R15") (pin "2") (pinfunction "P$2_2") (pintype "passive"))
      (node (ref "U$1") (pin "A11") (pinfunction "A11_A11") (pintype "bidirectional"))
    )
    (net (code "8") (name "ACT_T2") (class "Default")
      (node (ref "C7") (pin "2") (pinfunction "P$2_2") (pintype "passive"))
      (node (ref "R53") (pin "2") (pinfunction "P$2_2") (pintype "passive"))
      (node (ref "U$1") (pin "23/A9") (pinfunction "23/A9/T/PWM_23/A9") (pintype "bidirectional"))
    )
    (net (code "9") (name "ACT_T3") (class "Default")
      (node (ref "C5") (pin "2") (pinfunction "P$2_2") (pintype "passive"))
      (node (ref "R71") (pin "2") (pinfunction "P$2_2") (pintype "passive"))
      (node (ref "U$1") (pin "21/A7") (pinfunction "21/A7/PWM_21/A7") (pintype "bidirectional"))
    )
    (net (code "10") (name "ACT_T4") (class "Default")
      (node (ref "C8") (pin "2") (pinfunction "P$2_2") (pintype "passive"))
      (node (ref "R89") (pin "2") (pinfunction "P$2_2") (pintype "passive"))
      (node (ref "U$1") (pin "19/A5") (pinfunction "19/A5/T/SCL0_19/A5") (pintype "bidirectional"))
    )
    (net (code "11") (name "AGND") (class "Default")
      (node (ref "C10") (pin "1") (pinfunction "P$1_1") (pintype "passive"))
      (node (ref "C11") (pin "1") (pinfunction "P$1_1") (pintype "passive"))
      (node (ref "C12") (pin "1") (pinfunction "P$1_1") (pintype "passive"))
      (node (ref "C13") (pin "1") (pinfunction "P$1_1") (pintype "passive"))
      (node (ref "C14") (pin "1") (pinfunction "P$1_1") (pintype "passive"))
      (node (ref "C15") (pin "1") (pinfunction "P$1_1") (pintype "passive"))
      (node (ref "C20") (pin "1") (pinfunction "P$1_1") (pintype "passive"))
      (node (ref "C21") (pin "1") (pinfunction "P$1_1") (pintype "passive"))
      (node (ref "C22") (pin "1") (pinfunction "P$1_1") (pintype "passive"))
      (node (ref "C23") (pin "1") (pinfunction "P$1_1") (pintype "passive"))
      (node (ref "C24") (pin "1") (pinfunction "P$1_1") (pintype "passive"))
      (node (ref "C25") (pin "1") (pinfunction "P$1_1") (pintype "passive"))
      (node (ref "C27") (pin "1") (pinfunction "P$1_1") (pintype "passive"))
      (node (ref "C3") (pin "1") (pinfunction "P$1_1") (pintype "passive"))
      (node (ref "C30") (pin "1") (pinfunction "P$1_1") (pintype "passive"))
      (node (ref "C4") (pin "1") (pinfunction "P$1_1") (pintype "passive"))
      (node (ref "C5") (pin "1") (pinfunction "P$1_1") (pintype "passive"))
      (node (ref "C6") (pin "1") (pinfunction "P$1_1") (pintype "passive"))
      (node (ref "C7") (pin "1") (pinfunction "P$1_1") (pintype "passive"))
      (node (ref "C8") (pin "1") (pinfunction "P$1_1") (pintype "passive"))
      (node (ref "C9") (pin "1") (pinfunction "P$1_1") (pintype "passive"))
      (node (ref "CP1") (pin "-") (pinfunction "-_-") (pintype "passive"))
      (node (ref "CP2") (pin "2") (pinfunction "2_2") (pintype "passive"))
      (node (ref "CP3") (pin "-") (pinfunction "-_-") (pintype "passive"))
      (node (ref "IC1") (pin "4") (pinfunction "V-_4") (pintype "power_in"))
      (node (ref "IC10") (pin "11") (pinfunction "GND_11") (pintype "power_in"))
      (node (ref "IC2") (pin "4") (pinfunction "V-_4") (pintype "power_in"))
      (node (ref "IC3") (pin "3") (pinfunction "GND_3") (pintype "power_in"))
      (node (ref "IC4") (pin "11") (pinfunction "GND_11") (pintype "power_in"))
      (node (ref "IC5") (pin "11") (pinfunction "GND_11") (pintype "power_in"))
      (node (ref "IC6") (pin "3") (pinfunction "GND_3") (pintype "bidirectional"))
      (node (ref "IC7") (pin "4") (pinfunction "V-_4") (pintype "power_in"))
      (node (ref "IC8") (pin "11") (pinfunction "GND_11") (pintype "power_in"))
      (node (ref "IC9") (pin "4") (pinfunction "V-_4") (pintype "power_in"))
      (node (ref "JP1") (pin "12") (pinfunction "12_12") (pintype "passive"))
      (node (ref "JP10") (pin "2") (pinfunction "2_2") (pintype "passive"))
      (node (ref "JP11") (pin "12") (pinfunction "12_12") (pintype "passive"))
      (node (ref "JP12") (pin "2") (pinfunction "2_2") (pintype "passive"))
      (node (ref "JP13") (pin "2") (pinfunction "2_2") (pintype "passive"))
      (node (ref "JP2") (pin "12") (pinfunction "12_12") (pintype "passive"))
      (node (ref "JP3") (pin "2") (pinfunction "2_2") (pintype "passive"))
      (node (ref "JP4") (pin "1") (pinfunction "1_1") (pintype "passive"))
      (node (ref "JP5") (pin "2") (pinfunction "2_2") (pintype "passive"))
      (node (ref "JP6") (pin "2") (pinfunction "2_2") (pintype "passive"))
      (node (ref "JP7") (pin "2") (pinfunction "2_2") (pintype "passive"))
      (node (ref "JP8") (pin "12") (pinfunction "12_12") (pintype "passive"))
      (node (ref "JP9") (pin "2") (pinfunction "2_2") (pintype "passive"))
      (node (ref "L3") (pin "1") (pinfunction "P$1_1") (pintype "passive"))
      (node (ref "R1") (pin "1") (pinfunction "P$1_1") (pintype "passive"))
      (node (ref "R21") (pin "P$1") (pinfunction "1_P$1") (pintype "passive"))
      (node (ref "R23") (pin "P$1") (pinfunction "1_P$1") (pintype "passive"))
      (node (ref "R25") (pin "P$1") (pinfunction "1_P$1") (pintype "passive"))
      (node (ref "R27") (pin "P$1") (pinfunction "1_P$1") (pintype "passive"))
      (node (ref "R3") (pin "1") (pinfunction "P$1_1") (pintype "passive"))
      (node (ref "R37") (pin "1") (pinfunction "P$1_1") (pintype "passive"))
      (node (ref "R39") (pin "1") (pinfunction "P$1_1") (pintype "passive"))
      (node (ref "R41") (pin "P$2") (pinfunction "2_P$2") (pintype "passive"))
      (node (ref "R41") (pin "P$3") (pinfunction "3_P$3") (pintype "passive"))
      (node (ref "R42") (pin "P$2") (pinfunction "2_P$2") (pintype "passive"))
      (node (ref "R42") (pin "P$3") (pinfunction "3_P$3") (pintype "passive"))
      (node (ref "R55") (pin "1") (pinfunction "P$1_1") (pintype "passive"))
      (node (ref "R57") (pin "1") (pinfunction "P$1_1") (pintype "passive"))
      (node (ref "R59") (pin "P$2") (pinfunction "2_P$2") (pintype "passive"))
      (node (ref "R59") (pin "P$3") (pinfunction "3_P$3") (pintype "passive"))
      (node (ref "R6") (pin "P$2") (pinfunction "2_P$2") (pintype "passive"))
      (node (ref "R6") (pin "P$3") (pinfunction "3_P$3") (pintype "passive"))
      (node (ref "R60") (pin "P$2") (pinfunction "2_P$2") (pintype "passive"))
      (node (ref "R60") (pin "P$3") (pinfunction "3_P$3") (pintype "passive"))
      (node (ref "R7") (pin "P$2") (pinfunction "2_P$2") (pintype "passive"))
      (node (ref "R7") (pin "P$3") (pinfunction "3_P$3") (pintype "passive"))
      (node (ref "R73") (pin "1") (pinfunction "P$1_1") (pintype "passive"))
      (node (ref "R75") (pin "1") (pinfunction "P$1_1") (pintype "passive"))
      (node (ref "R77") (pin "P$2") (pinfunction "2_P$2") (pintype "passive"))
      (node (ref "R77") (pin "P$3") (pinfunction "3_P$3") (pintype "passive"))
      (node (ref "R78") (pin "P$2") (pinfunction "2_P$2") (pintype "passive"))
      (node (ref "R78") (pin "P$3") (pinfunction "3_P$3") (pintype "passive"))
      (node (ref "S1") (pin "P$2") (pinfunction "2_P$2") (pintype "bidirectional"))
      (node (ref "S1") (pin "P$5") (pinfunction "5_P$5") (pintype "bidirectional"))
      (node (ref "S2") (pin "P$2") (pinfunction "2_P$2") (pintype "bidirectional"))
      (node (ref "S2") (pin "P$5") (pinfunction "5_P$5") (pintype "bidirectional"))
      (node (ref "S3") (pin "P$2") (pinfunction "2_P$2") (pintype "bidirectional"))
      (node (ref "S3") (pin "P$5") (pinfunction "5_P$5") (pintype "bidirectional"))
      (node (ref "S4") (pin "P$2") (pinfunction "2_P$2") (pintype "bidirectional"))
      (node (ref "S4") (pin "P$5") (pinfunction "5_P$5") (pintype "bidirectional"))
      (node (ref "T1") (pin "2") (pinfunction "E_2") (pintype "passive"))
      (node (ref "T2") (pin "2") (pinfunction "E_2") (pintype "passive"))
      (node (ref "T3") (pin "2") (pinfunction "E_2") (pintype "passive"))
      (node (ref "T4") (pin "2") (pinfunction "E_2") (pintype "passive"))
      (node (ref "T5") (pin "2") (pinfunction "E_2") (pintype "passive"))
      (node (ref "T6") (pin "2") (pinfunction "E_2") (pintype "passive"))
      (node (ref "T7") (pin "2") (pinfunction "E_2") (pintype "passive"))
      (node (ref "T8") (pin "2") (pinfunction "E_2") (pintype "passive"))
      (node (ref "TP27") (pin "P$1") (pinfunction "P$1_P$1") (pintype "bidirectional"))
      (node (ref "U$1") (pin "AGND") (pinfunction "AGND_AGND") (pintype "power_in"))
      (node (ref "X1") (pin "2") (pinfunction "2_2") (pintype "passive"))
      (node (ref "X2") (pin "2") (pinfunction "2_2") (pintype "passive"))
      (node (ref "X3") (pin "2") (pinfunction "2_2") (pintype "passive"))
      (node (ref "X4") (pin "2") (pinfunction "2_2") (pintype "passive"))
      (node (ref "X5") (pin "2") (pinfunction "2_2") (pintype "passive"))
      (node (ref "X6") (pin "2") (pinfunction "2_2") (pintype "passive"))
      (node (ref "X7") (pin "2") (pinfunction "2_2") (pintype "passive"))
      (node (ref "X8") (pin "2") (pinfunction "2_2") (pintype "passive"))
    )
    (net (code "12") (name "CS_DAC") (class "Default")
      (node (ref "IC3") (pin "6") (pinfunction "SYNC_6") (pintype "bidirectional"))
      (node (ref "U$1") (pin "6") (pinfunction "6/PWM_6") (pintype "bidirectional"))
    )
    (net (code "13") (name "CS_LCD") (class "Default")
      (node (ref "LCD_HEADER") (pin "6") (pinfunction "6_6") (pintype "passive"))
      (node (ref "U$1") (pin "12") (pinfunction "12/MISO_12") (pintype "bidirectional"))
    )
    (net (code "14") (name "CS_POT1") (class "Default")
      (node (ref "IC4") (pin "9") (pinfunction "CS_9") (pintype "bidirectional"))
      (node (ref "U$1") (pin "2") (pinfunction "2_2") (pintype "bidirectional"))
    )
    (net (code "15") (name "CS_POT2") (class "Default")
      (node (ref "IC5") (pin "9") (pinfunction "CS_9") (pintype "bidirectional"))
      (node (ref "U$1") (pin "3") (pinfunction "3/CAN-TX/PWM_3") (pintype "bidirectional"))
    )
    (net (code "16") (name "CS_POT3") (class "Default")
      (node (ref "IC8") (pin "9") (pinfunction "CS_9") (pintype "bidirectional"))
      (node (ref "U$1") (pin "4") (pinfunction "4/CAN-RX-PWM_4") (pintype "bidirectional"))
    )
    (net (code "17") (name "CS_POT4") (class "Default")
      (node (ref "IC10") (pin "9") (pinfunction "CS_9") (pintype "bidirectional"))
      (node (ref "U$1") (pin "5") (pinfunction "5/PWM_5") (pintype "bidirectional"))
    )
    (net (code "18") (name "ENC_A1") (class "Default")
      (node (ref "C17") (pin "2") (pinfunction "2_2") (pintype "passive"))
      (node (ref "ENC1") (pin "A") (pinfunction "A_A") (pintype "bidirectional"))
      (node (ref "R28") (pin "P$1") (pinfunction "1_P$1") (pintype "passive"))
      (node (ref "U$1") (pin "17/A3") (pinfunction "17/A3/T_17/A3") (pintype "bidirectional"))
    )
    (net (code "19") (name "ENC_A2") (class "Default")
      (node (ref "C19") (pin "2") (pinfunction "2_2") (pintype "passive"))
      (node (ref "ENC2") (pin "A") (pinfunction "A_A") (pintype "bidirectional"))
      (node (ref "R33") (pin "P$1") (pinfunction "1_P$1") (pintype "passive"))
      (node (ref "U$1") (pin "14/A0") (pinfunction "14/A0_14/A0") (pintype "bidirectional"))
    )
    (net (code "20") (name "ENC_B1") (class "Default")
      (node (ref "C16") (pin "2") (pinfunction "2_2") (pintype "passive"))
      (node (ref "ENC1") (pin "B") (pinfunction "B_B") (pintype "bidirectional"))
      (node (ref "R19") (pin "1") (pinfunction "P$1_1") (pintype "passive"))
      (node (ref "U$1") (pin "7") (pinfunction "7/RX3_7") (pintype "bidirectional"))
    )
    (net (code "21") (name "ENC_B2") (class "Default")
      (node (ref "C18") (pin "2") (pinfunction "2_2") (pintype "passive"))
      (node (ref "ENC2") (pin "B") (pinfunction "B_B") (pintype "bidirectional"))
      (node (ref "R32") (pin "1") (pinfunction "P$1_1") (pintype "passive"))
      (node (ref "U$1") (pin "16/A2") (pinfunction "16/A2/T_16/A2") (pintype "bidirectional"))
    )
    (net (code "22") (name "ENC_SW1") (class "Default")
      (node (ref "ENC1") (pin "E") (pinfunction "E_E") (pintype "bidirectional"))
      (node (ref "R29") (pin "1") (pinfunction "P$1_1") (pintype "passive"))
      (node (ref "U$1") (pin "8") (pinfunction "8/TX3_8") (pintype "bidirectional"))
    )
    (net (code "23") (name "ENC_SW2") (class "Default")
      (node (ref "ENC2") (pin "E") (pinfunction "E_E") (pintype "bidirectional"))
      (node (ref "R34") (pin "1") (pinfunction "P$1_1") (pintype "passive"))
      (node (ref "U$1") (pin "15/A1") (pinfunction "15/A1/T_15/A1") (pintype "bidirectional"))
    )
    (net (code "24") (name "GND") (class "Default")
      (node (ref "C1") (pin "1") (pinfunction "P$1_1") (pintype "passive"))
      (node (ref "C16") (pin "1") (pinfunction "1_1") (pintype "passive"))
      (node (ref "C17") (pin "1") (pinfunction "1_1") (pintype "passive"))
      (node (ref "C18") (pin "1") (pinfunction "1_1") (pintype "passive"))
      (node (ref "C19") (pin "1") (pinfunction "1_1") (pintype "passive"))
      (node (ref "C2") (pin "1") (pinfunction "P$1_1") (pintype "passive"))
      (node (ref "IC10") (pin "12") (pinfunction "VSS_12") (pintype "power_in"))
      (node (ref "IC4") (pin "12") (pinfunction "VSS_12") (pintype "power_in"))
      (node (ref "IC5") (pin "12") (pinfunction "VSS_12") (pintype "power_in"))
      (node (ref "IC8") (pin "12") (pinfunction "VSS_12") (pintype "power_in"))
      (node (ref "L3") (pin "2") (pinfunction "P$2_2") (pintype "passive"))
      (node (ref "LCD_HEADER") (pin "2") (pinfunction "2_2") (pintype "passive"))
      (node (ref "LCD_HEADER") (pin "4") (pinfunction "4_4") (pintype "passive"))
      (node (ref "R30") (pin "1") (pinfunction "P$1_1") (pintype "passive"))
      (node (ref "R31") (pin "1") (pinfunction "P$1_1") (pintype "passive"))
      (node (ref "R35") (pin "1") (pinfunction "P$1_1") (pintype "passive"))
      (node (ref "R36") (pin "1") (pinfunction "P$1_1") (pintype "passive"))
      (node (ref "U$1") (pin "GND") (pinfunction "GND_GND") (pintype "power_in"))
      (node (ref "U$1") (pin "GND1") (pinfunction "GND_GND1") (pintype "power_in"))
    )
    (net (code "25") (name "I1") (class "Default")
      (node (ref "IC4") (pin "16") (pinfunction "A2_16") (pintype "bidirectional"))
      (node (ref "JP1") (pin "5") (pinfunction "5_5") (pintype "passive"))
      (node (ref "TP6") (pin "P$1") (pinfunction "P$1_P$1") (pintype "bidirectional"))
    )
    (net (code "26") (name "I2") (class "Default")
      (node (ref "IC5") (pin "16") (pinfunction "A2_16") (pintype "bidirectional"))
      (node (ref "JP2") (pin "5") (pinfunction "5_5") (pintype "passive"))
      (node (ref "TP13") (pin "P$1") (pinfunction "P$1_P$1") (pintype "bidirectional"))
    )
    (net (code "27") (name "I3") (class "Default")
      (node (ref "IC8") (pin "16") (pinfunction "A2_16") (pintype "bidirectional"))
      (node (ref "JP8") (pin "5") (pinfunction "5_5") (pintype "passive"))
      (node (ref "TP19") (pin "P$1") (pinfunction "P$1_P$1") (pintype "bidirectional"))
    )
    (net (code "28") (name "I4") (class "Default")
      (node (ref "IC10") (pin "16") (pinfunction "A2_16") (pintype "bidirectional"))
      (node (ref "JP11") (pin "5") (pinfunction "5_5") (pintype "passive"))
      (node (ref "TP25") (pin "P$1") (pinfunction "P$1_P$1") (pintype "bidirectional"))
    )
    (net (code "29") (name "LIMA1") (class "Default")
      (node (ref "JP1") (pin "4") (pinfunction "4_4") (pintype "passive"))
      (node (ref "R2") (pin "2") (pinfunction "P$2_2") (pintype "passive"))
      (node (ref "T1") (pin "3") (pinfunction "C_3") (pintype "passive"))
    )
    (net (code "30") (name "LIMA2") (class "Default")
      (node (ref "JP2") (pin "4") (pinfunction "4_4") (pintype "passive"))
      (node (ref "R38") (pin "2") (pinfunction "P$2_2") (pintype "passive"))
      (node (ref "T3") (pin "3") (pinfunction "C_3") (pintype "passive"))
    )
    (net (code "31") (name "LIMA3") (class "Default")
      (node (ref "JP8") (pin "4") (pinfunction "4_4") (pintype "passive"))
      (node (ref "R56") (pin "2") (pinfunction "P$2_2") (pintype "passive"))
      (node (ref "T5") (pin "3") (pinfunction "C_3") (pintype "passive"))
    )
    (net (code "32") (name "LIMA4") (class "Default")
      (node (ref "JP11") (pin "4") (pinfunction "4_4") (pintype "passive"))
      (node (ref "R74") (pin "2") (pinfunction "P$2_2") (pintype "passive"))
      (node (ref "T7") (pin "3") (pinfunction "C_3") (pintype "passive"))
    )
    (net (code "33") (name "LIMB1") (class "Default")
      (node (ref "JP1") (pin "6") (pinfunction "6_6") (pintype "passive"))
      (node (ref "R4") (pin "2") (pinfunction "P$2_2") (pintype "passive"))
      (node (ref "T2") (pin "3") (pinfunction "C_3") (pintype "passive"))
    )
    (net (code "34") (name "LIMB2") (class "Default")
      (node (ref "JP2") (pin "6") (pinfunction "6_6") (pintype "passive"))
      (node (ref "R40") (pin "2") (pinfunction "P$2_2") (pintype "passive"))
      (node (ref "T4") (pin "3") (pinfunction "C_3") (pintype "passive"))
    )
    (net (code "35") (name "LIMB3") (class "Default")
      (node (ref "JP8") (pin "6") (pinfunction "6_6") (pintype "passive"))
      (node (ref "R58") (pin "2") (pinfunction "P$2_2") (pintype "passive"))
      (node (ref "T6") (pin "3") (pinfunction "C_3") (pintype "passive"))
    )
    (net (code "36") (name "LIMB4") (class "Default")
      (node (ref "JP11") (pin "6") (pinfunction "6_6") (pintype "passive"))
      (node (ref "R76") (pin "2") (pinfunction "P$2_2") (pintype "passive"))
      (node (ref "T8") (pin "3") (pinfunction "C_3") (pintype "passive"))
    )
    (net (code "37") (name "MON") (class "Default")
      (node (ref "U$1") (pin "A14") (pinfunction "A14/DAC_A14") (pintype "bidirectional"))
    )
    (net (code "38") (name "MOSI") (class "Default")
      (node (ref "LCD_HEADER") (pin "3") (pinfunction "3_3") (pintype "passive"))
      (node (ref "U$1") (pin "11") (pinfunction "11/MOSI_11") (pintype "bidirectional"))
    )
    (net (code "39") (name "MOSI_B") (class "Default")
      (node (ref "IC10") (pin "8") (pinfunction "SDI_8") (pintype "bidirectional"))
      (node (ref "IC3") (pin "8") (pinfunction "DIN_8") (pintype "bidirectional"))
      (node (ref "IC4") (pin "8") (pinfunction "SDI_8") (pintype "bidirectional"))
      (node (ref "IC5") (pin "8") (pinfunction "SDI_8") (pintype "bidirectional"))
      (node (ref "IC8") (pin "8") (pinfunction "SDI_8") (pintype "bidirectional"))
      (node (ref "U$1") (pin "0") (pinfunction "0/RX1/T_0") (pintype "bidirectional"))
    )
    (net (code "40") (name "Net-(C1-P$2)") (class "Default")
      (node (ref "C1") (pin "2") (pinfunction "P$2_2") (pintype "passive"))
      (node (ref "C2") (pin "2") (pinfunction "P$2_2") (pintype "passive"))
      (node (ref "L2") (pin "1") (pinfunction "P$1_1") (pintype "passive"))
      (node (ref "U$1") (pin "VIN") (pinfunction "VIN_VIN") (pintype "power_in"))
    )
    (net (code "41") (name "Net-(C27-P$2)") (class "Default")
      (node (ref "C27") (pin "2") (pinfunction "P$2_2") (pintype "passive"))
      (node (ref "C30") (pin "2") (pinfunction "P$2_2") (pintype "passive"))
      (node (ref "IC3") (pin "9") (pinfunction "VDD_9") (pintype "power_in"))
      (node (ref "L1") (pin "1") (pinfunction "P$1_1") (pintype "passive"))
    )
    (net (code "42") (name "Net-(ENC1-GND)") (class "Default")
      (node (ref "ENC1") (pin "C") (pinfunction "GND_C") (pintype "bidirectional"))
      (node (ref "R30") (pin "2") (pinfunction "P$2_2") (pintype "passive"))
    )
    (net (code "43") (name "Net-(ENC2-GND)") (class "Default")
      (node (ref "ENC2") (pin "C") (pinfunction "GND_C") (pintype "bidirectional"))
      (node (ref "R35") (pin "2") (pinfunction "P$2_2") (pintype "passive"))
    )
    (net (code "44") (name "Net-(IC1A--IN)") (class "Default")
      (node (ref "IC1") (pin "2") (pinfunction "-IN_2") (pintype "input"))
      (node (ref "R6") (pin "P$1") (pinfunction "1_P$1") (pintype "passive"))
      (node (ref "R8") (pin "1") (pinfunction "P$1_1") (pintype "passive"))
      (node (ref "TP2") (pin "P$1") (pinfunction "P$1_P$1") (pintype "bidirectional"))
    )
    (net (code "45") (name "Net-(IC1A-OUT)") (class "Default")
      (node (ref "IC1") (pin "1") (pinfunction "OUT_1") (pintype "output"))
      (node (ref "R10") (pin "2") (pinfunction "P$2_2") (pintype "passive"))
      (node (ref "R9") (pin "1") (pinfunction "P$1_1") (pintype "passive"))
    )
    (net (code "46") (name "Net-(IC1B-+IN)") (class "Default")
      (node (ref "IC1") (pin "5") (pinfunction "+IN_5") (pintype "input"))
      (node (ref "R11") (pin "1") (pinfunction "P$1_1") (pintype "passive"))
      (node (ref "R7") (pin "P$1") (pinfunction "1_P$1") (pintype "passive"))
      (node (ref "TP3") (pin "P$1") (pinfunction "P$1_P$1") (pintype "bidirectional"))
    )
    (net (code "47") (name "Net-(IC1B-OUT)") (class "Default")
      (node (ref "IC1") (pin "7") (pinfunction "OUT_7") (pintype "output"))
      (node (ref "R12") (pin "1") (pinfunction "P$1_1") (pintype "passive"))
      (node (ref "R13") (pin "2") (pinfunction "P$2_2") (pintype "passive"))
    )
    (net (code "48") (name "Net-(IC2A--IN)") (class "Default")
      (node (ref "IC2") (pin "2") (pinfunction "-IN_2") (pintype "input"))
      (node (ref "R41") (pin "P$1") (pinfunction "1_P$1") (pintype "passive"))
      (node (ref "R43") (pin "1") (pinfunction "P$1_1") (pintype "passive"))
      (node (ref "TP9") (pin "P$1") (pinfunction "P$1_P$1") (pintype "bidirectional"))
    )
    (net (code "49") (name "Net-(IC2A-OUT)") (class "Default")
      (node (ref "IC2") (pin "1") (pinfunction "OUT_1") (pintype "output"))
      (node (ref "R44") (pin "1") (pinfunction "P$1_1") (pintype "passive"))
      (node (ref "R45") (pin "2") (pinfunction "P$2_2") (pintype "passive"))
    )
    (net (code "50") (name "Net-(IC2B-+IN)") (class "Default")
      (node (ref "IC2") (pin "5") (pinfunction "+IN_5") (pintype "input"))
      (node (ref "R42") (pin "P$1") (pinfunction "1_P$1") (pintype "passive"))
      (node (ref "R46") (pin "1") (pinfunction "P$1_1") (pintype "passive"))
      (node (ref "TP10") (pin "P$1") (pinfunction "P$1_P$1") (pintype "bidirectional"))
    )
    (net (code "51") (name "Net-(IC2B-OUT)") (class "Default")
      (node (ref "IC2") (pin "7") (pinfunction "OUT_7") (pintype "output"))
      (node (ref "R47") (pin "1") (pinfunction "P$1_1") (pintype "passive"))
      (node (ref "R48") (pin "2") (pinfunction "P$2_2") (pintype "passive"))
    )
    (net (code "52") (name "Net-(IC3-VREF)") (class "Default")
      (node (ref "IC3") (pin "10") (pinfunction "VREF_10") (pintype "bidirectional"))
      (node (ref "JP14") (pin "1") (pinfunction "1_1") (pintype "passive"))
      (node (ref "TP1") (pin "P$1") (pinfunction "P$1_P$1") (pintype "bidirectional"))
    )
    (net (code "53") (name "Net-(IC7A--IN)") (class "Default")
      (node (ref "IC7") (pin "2") (pinfunction "-IN_2") (pintype "input"))
      (node (ref "R59") (pin "P$1") (pinfunction "1_P$1") (pintype "passive"))
      (node (ref "R61") (pin "1") (pinfunction "P$1_1") (pintype "passive"))
      (node (ref "TP15") (pin "P$1") (pinfunction "P$1_P$1") (pintype "bidirectional"))
    )
    (net (code "54") (name "Net-(IC7A-OUT)") (class "Default")
      (node (ref "IC7") (pin "1") (pinfunction "OUT_1") (pintype "output"))
      (node (ref "R62") (pin "1") (pinfunction "P$1_1") (pintype "passive"))
      (node (ref "R63") (pin "2") (pinfunction "P$2_2") (pintype "passive"))
    )
    (net (code "55") (name "Net-(IC7B-+IN)") (class "Default")
      (node (ref "IC7") (pin "5") (pinfunction "+IN_5") (pintype "input"))
      (node (ref "R60") (pin "P$1") (pinfunction "1_P$1") (pintype "passive"))
      (node (ref "R64") (pin "1") (pinfunction "P$1_1") (pintype "passive"))
      (node (ref "TP16") (pin "P$1") (pinfunction "P$1_P$1") (pintype "bidirectional"))
    )
    (net (code "56") (name "Net-(IC7B-OUT)") (class "Default")
      (node (ref "IC7") (pin "7") (pinfunction "OUT_7") (pintype "output"))
      (node (ref "R65") (pin "1") (pinfunction "P$1_1") (pintype "passive"))
      (node (ref "R66") (pin "2") (pinfunction "P$2_2") (pintype "passive"))
    )
    (net (code "57") (name "Net-(IC9A--IN)") (class "Default")
      (node (ref "IC9") (pin "2") (pinfunction "-IN_2") (pintype "input"))
      (node (ref "R77") (pin "P$1") (pinfunction "1_P$1") (pintype "passive"))
      (node (ref "R79") (pin "1") (pinfunction "P$1_1") (pintype "passive"))
      (node (ref "TP21") (pin "P$1") (pinfunction "P$1_P$1") (pintype "bidirectional"))
    )
    (net (code "58") (name "Net-(IC9A-OUT)") (class "Default")
      (node (ref "IC9") (pin "1") (pinfunction "OUT_1") (pintype "output"))
      (node (ref "R80") (pin "1") (pinfunction "P$1_1") (pintype "passive"))
      (node (ref "R81") (pin "2") (pinfunction "P$2_2") (pintype "passive"))
    )
    (net (code "59") (name "Net-(IC9B-+IN)") (class "Default")
      (node (ref "IC9") (pin "5") (pinfunction "+IN_5") (pintype "input"))
      (node (ref "R78") (pin "P$1") (pinfunction "1_P$1") (pintype "passive"))
      (node (ref "R82") (pin "1") (pinfunction "P$1_1") (pintype "passive"))
      (node (ref "TP22") (pin "P$1") (pinfunction "P$1_P$1") (pintype "bidirectional"))
    )
    (net (code "60") (name "Net-(IC9B-OUT)") (class "Default")
      (node (ref "IC9") (pin "7") (pinfunction "OUT_7") (pintype "output"))
      (node (ref "R83") (pin "1") (pinfunction "P$1_1") (pintype "passive"))
      (node (ref "R84") (pin "2") (pinfunction "P$2_2") (pintype "passive"))
    )
    (net (code "61") (name "Net-(LCD_HEADER-Pad1)") (class "Default")
      (node (ref "LCD_HEADER") (pin "1") (pinfunction "1_1") (pintype "passive"))
      (node (ref "U$1") (pin "3.3V") (pinfunction "3.3V_3.3V") (pintype "power_in"))
      (node (ref "U$1") (pin "3.3V1") (pinfunction "3.3V_3.3V1") (pintype "power_in"))
    )
    (net (code "62") (name "Net-(R1-P$2)") (class "Default")
      (node (ref "JP3") (pin "1") (pinfunction "1_1") (pintype "passive"))
      (node (ref "R1") (pin "2") (pinfunction "P$2_2") (pintype "passive"))
      (node (ref "R2") (pin "1") (pinfunction "P$1_1") (pintype "passive"))
      (node (ref "S1") (pin "P$3") (pinfunction "3_P$3") (pintype "bidirectional"))
    )
    (net (code "63") (name "Net-(R3-P$2)") (class "Default")
      (node (ref "JP5") (pin "1") (pinfunction "1_1") (pintype "passive"))
      (node (ref "R3") (pin "2") (pinfunction "P$2_2") (pintype "passive"))
      (node (ref "R4") (pin "1") (pinfunction "P$1_1") (pintype "passive"))
      (node (ref "S1") (pin "P$6") (pinfunction "6_P$6") (pintype "bidirectional"))
    )
    (net (code "64") (name "Net-(R5-P$1)") (class "Default")
      (node (ref "R5") (pin "1") (pinfunction "P$1_1") (pintype "passive"))
      (node (ref "S1") (pin "P$4") (pinfunction "4_P$4") (pintype "bidirectional"))
    )
    (net (code "65") (name "Net-(R5-P$2)") (class "Default")
      (node (ref "D1") (pin "C") (pinfunction "C_C") (pintype "bidirectional"))
      (node (ref "R5") (pin "2") (pinfunction "P$2_2") (pintype "passive"))
    )
    (net (code "66") (name "Net-(R10-P$1)") (class "Default")
      (node (ref "R10") (pin "1") (pinfunction "P$1_1") (pintype "passive"))
      (node (ref "T1") (pin "1") (pinfunction "B_1") (pintype "passive"))
    )
    (net (code "67") (name "Net-(R13-P$1)") (class "Default")
      (node (ref "R13") (pin "1") (pinfunction "P$1_1") (pintype "passive"))
      (node (ref "T2") (pin "1") (pinfunction "B_1") (pintype "passive"))
    )
    (net (code "68") (name "Net-(R14-P$1)") (class "Default")
      (node (ref "JP1") (pin "8") (pinfunction "8_8") (pintype "passive"))
      (node (ref "R14") (pin "1") (pinfunction "P$1_1") (pintype "passive"))
      (node (ref "R15") (pin "1") (pinfunction "P$1_1") (pintype "passive"))
    )
    (net (code "69") (name "Net-(R14-P$2)") (class "Default")
      (node (ref "R14") (pin "2") (pinfunction "P$2_2") (pintype "passive"))
      (node (ref "X1") (pin "1") (pinfunction "1_1") (pintype "passive"))
    )
    (net (code "70") (name "Net-(R18-P$2)") (class "Default")
      (node (ref "R18") (pin "2") (pinfunction "P$2_2") (pintype "passive"))
      (node (ref "X2") (pin "1") (pinfunction "1_1") (pintype "passive"))
    )
    (net (code "71") (name "Net-(R31-P$2)") (class "Default")
      (node (ref "ENC1") (pin "D") (pinfunction "D_D") (pintype "bidirectional"))
      (node (ref "R31") (pin "2") (pinfunction "P$2_2") (pintype "passive"))
    )
    (net (code "72") (name "Net-(R36-P$2)") (class "Default")
      (node (ref "ENC2") (pin "D") (pinfunction "D_D") (pintype "bidirectional"))
      (node (ref "R36") (pin "2") (pinfunction "P$2_2") (pintype "passive"))
    )
    (net (code "73") (name "Net-(R37-P$2)") (class "Default")
      (node (ref "JP6") (pin "1") (pinfunction "1_1") (pintype "passive"))
      (node (ref "R37") (pin "2") (pinfunction "P$2_2") (pintype "passive"))
      (node (ref "R38") (pin "1") (pinfunction "P$1_1") (pintype "passive"))
      (node (ref "S2") (pin "P$3") (pinfunction "3_P$3") (pintype "bidirectional"))
    )
    (net (code "74") (name "Net-(R39-P$2)") (class "Default")
      (node (ref "JP7") (pin "1") (pinfunction "1_1") (pintype "passive"))
      (node (ref "R39") (pin "2") (pinfunction "P$2_2") (pintype "passive"))
      (node (ref "R40") (pin "1") (pinfunction "P$1_1") (pintype "passive"))
      (node (ref "S2") (pin "P$6") (pinfunction "6_P$6") (pintype "bidirectional"))
    )
    (net (code "75") (name "Net-(R45-P$1)") (class "Default")
      (node (ref "R45") (pin "1") (pinfunction "P$1_1") (pintype "passive"))
      (node (ref "T3") (pin "1") (pinfunction "B_1") (pintype "passive"))
    )
    (net (code "76") (name "Net-(R48-P$1)") (class "Default")
      (node (ref "R48") (pin "1") (pinfunction "P$1_1") (pintype "passive"))
      (node (ref "T4") (pin "1") (pinfunction "B_1") (pintype "passive"))
    )
    (net (code "77") (name "Net-(R49-P$1)") (class "Default")
      (node (ref "R49") (pin "1") (pinfunction "P$1_1") (pintype "passive"))
      (node (ref "S2") (pin "P$4") (pinfunction "4_P$4") (pintype "bidirectional"))
    )
    (net (code "78") (name "Net-(R49-P$2)") (class "Default")
      (node (ref "D2") (pin "C") (pinfunction "C_C") (pintype "bidirectional"))
      (node (ref "R49") (pin "2") (pinfunction "P$2_2") (pintype "passive"))
    )
    (net (code "79") (name "Net-(R52-P$1)") (class "Default")
      (node (ref "JP2") (pin "8") (pinfunction "8_8") (pintype "passive"))
      (node (ref "R52") (pin "1") (pinfunction "P$1_1") (pintype "passive"))
      (node (ref "R53") (pin "1") (pinfunction "P$1_1") (pintype "passive"))
    )
    (net (code "80") (name "Net-(R52-P$2)") (class "Default")
      (node (ref "R52") (pin "2") (pinfunction "P$2_2") (pintype "passive"))
      (node (ref "X3") (pin "1") (pinfunction "1_1") (pintype "passive"))
    )
    (net (code "81") (name "Net-(R54-P$2)") (class "Default")
      (node (ref "R54") (pin "2") (pinfunction "P$2_2") (pintype "passive"))
      (node (ref "X4") (pin "1") (pinfunction "1_1") (pintype "passive"))
    )
    (net (code "82") (name "Net-(R55-P$2)") (class "Default")
      (node (ref "JP9") (pin "1") (pinfunction "1_1") (pintype "passive"))
      (node (ref "R55") (pin "2") (pinfunction "P$2_2") (pintype "passive"))
      (node (ref "R56") (pin "1") (pinfunction "P$1_1") (pintype "passive"))
      (node (ref "S3") (pin "P$3") (pinfunction "3_P$3") (pintype "bidirectional"))
    )
    (net (code "83") (name "Net-(R57-P$2)") (class "Default")
      (node (ref "JP10") (pin "1") (pinfunction "1_1") (pintype "passive"))
      (node (ref "R57") (pin "2") (pinfunction "P$2_2") (pintype "passive"))
      (node (ref "R58") (pin "1") (pinfunction "P$1_1") (pintype "passive"))
      (node (ref "S3") (pin "P$6") (pinfunction "6_P$6") (pintype "bidirectional"))
    )
    (net (code "84") (name "Net-(R63-P$1)") (class "Default")
      (node (ref "R63") (pin "1") (pinfunction "P$1_1") (pintype "passive"))
      (node (ref "T5") (pin "1") (pinfunction "B_1") (pintype "passive"))
    )
    (net (code "85") (name "Net-(R66-P$1)") (class "Default")
      (node (ref "R66") (pin "1") (pinfunction "P$1_1") (pintype "passive"))
      (node (ref "T6") (pin "1") (pinfunction "B_1") (pintype "passive"))
    )
    (net (code "86") (name "Net-(R67-P$1)") (class "Default")
      (node (ref "R67") (pin "1") (pinfunction "P$1_1") (pintype "passive"))
      (node (ref "S3") (pin "P$4") (pinfunction "4_P$4") (pintype "bidirectional"))
    )
    (net (code "87") (name "Net-(R67-P$2)") (class "Default")
      (node (ref "D3") (pin "C") (pinfunction "C_C") (pintype "bidirectional"))
      (node (ref "R67") (pin "2") (pinfunction "P$2_2") (pintype "passive"))
    )
    (net (code "88") (name "Net-(R70-P$1)") (class "Default")
      (node (ref "JP8") (pin "8") (pinfunction "8_8") (pintype "passive"))
      (node (ref "R70") (pin "1") (pinfunction "P$1_1") (pintype "passive"))
      (node (ref "R71") (pin "1") (pinfunction "P$1_1") (pintype "passive"))
    )
    (net (code "89") (name "Net-(R70-P$2)") (class "Default")
      (node (ref "R70") (pin "2") (pinfunction "P$2_2") (pintype "passive"))
      (node (ref "X5") (pin "1") (pinfunction "1_1") (pintype "passive"))
    )
    (net (code "90") (name "Net-(R72-P$2)") (class "Default")
      (node (ref "R72") (pin "2") (pinfunction "P$2_2") (pintype "passive"))
      (node (ref "X6") (pin "1") (pinfunction "1_1") (pintype "passive"))
    )
    (net (code "91") (name "Net-(R73-P$2)") (class "Default")
      (node (ref "JP12") (pin "1") (pinfunction "1_1") (pintype "passive"))
      (node (ref "R73") (pin "2") (pinfunction "P$2_2") (pintype "passive"))
      (node (ref "R74") (pin "1") (pinfunction "P$1_1") (pintype "passive"))
      (node (ref "S4") (pin "P$3") (pinfunction "3_P$3") (pintype "bidirectional"))
    )
    (net (code "92") (name "Net-(R75-P$2)") (class "Default")
      (node (ref "JP13") (pin "1") (pinfunction "1_1") (pintype "passive"))
      (node (ref "R75") (pin "2") (pinfunction "P$2_2") (pintype "passive"))
      (node (ref "R76") (pin "1") (pinfunction "P$1_1") (pintype "passive"))
      (node (ref "S4") (pin "P$6") (pinfunction "6_P$6") (pintype "bidirectional"))
    )
    (net (code "93") (name "Net-(R81-P$1)") (class "Default")
      (node (ref "R81") (pin "1") (pinfunction "P$1_1") (pintype "passive"))
      (node (ref "T7") (pin "1") (pinfunction "B_1") (pintype "passive"))
    )
    (net (code "94") (name "Net-(R84-P$1)") (class "Default")
      (node (ref "R84") (pin "1") (pinfunction "P$1_1") (pintype "passive"))
      (node (ref "T8") (pin "1") (pinfunction "B_1") (pintype "passive"))
    )
    (net (code "95") (name "Net-(R85-P$1)") (class "Default")
      (node (ref "R85") (pin "1") (pinfunction "P$1_1") (pintype "passive"))
      (node (ref "S4") (pin "P$4") (pinfunction "4_P$4") (pintype "bidirectional"))
    )
    (net (code "96") (name "Net-(R85-P$2)") (class "Default")
      (node (ref "D4") (pin "C") (pinfunction "C_C") (pintype "bidirectional"))
      (node (ref "R85") (pin "2") (pinfunction "P$2_2") (pintype "passive"))
    )
    (net (code "97") (name "Net-(R88-P$1)") (class "Default")
      (node (ref "JP11") (pin "8") (pinfunction "8_8") (pintype "passive"))
      (node (ref "R88") (pin "1") (pinfunction "P$1_1") (pintype "passive"))
      (node (ref "R89") (pin "1") (pinfunction "P$1_1") (pintype "passive"))
    )
    (net (code "98") (name "Net-(R88-P$2)") (class "Default")
      (node (ref "R88") (pin "2") (pinfunction "P$2_2") (pintype "passive"))
      (node (ref "X7") (pin "1") (pinfunction "1_1") (pintype "passive"))
    )
    (net (code "99") (name "Net-(R90-P$2)") (class "Default")
      (node (ref "R90") (pin "2") (pinfunction "P$2_2") (pintype "passive"))
      (node (ref "X8") (pin "1") (pinfunction "1_1") (pintype "passive"))
    )
    (net (code "100") (name "P1") (class "Default")
      (node (ref "IC4") (pin "2") (pinfunction "A1_2") (pintype "bidirectional"))
      (node (ref "JP1") (pin "1") (pinfunction "1_1") (pintype "passive"))
      (node (ref "TP4") (pin "P$1") (pinfunction "P$1_P$1") (pintype "bidirectional"))
    )
    (net (code "101") (name "P2") (class "Default")
      (node (ref "IC5") (pin "2") (pinfunction "A1_2") (pintype "bidirectional"))
      (node (ref "JP2") (pin "1") (pinfunction "1_1") (pintype "passive"))
      (node (ref "TP11") (pin "P$1") (pinfunction "P$1_P$1") (pintype "bidirectional"))
    )
    (net (code "102") (name "P3") (class "Default")
      (node (ref "IC8") (pin "2") (pinfunction "A1_2") (pintype "bidirectional"))
      (node (ref "JP8") (pin "1") (pinfunction "1_1") (pintype "passive"))
      (node (ref "TP17") (pin "P$1") (pinfunction "P$1_P$1") (pintype "bidirectional"))
    )
    (net (code "103") (name "P4") (class "Default")
      (node (ref "IC10") (pin "2") (pinfunction "A1_2") (pintype "bidirectional"))
      (node (ref "JP11") (pin "1") (pinfunction "1_1") (pintype "passive"))
      (node (ref "TP23") (pin "P$1") (pinfunction "P$1_P$1") (pintype "bidirectional"))
    )
    (net (code "104") (name "RST_LCD") (class "Default")
      (node (ref "LCD_HEADER") (pin "8") (pinfunction "8_8") (pintype "passive"))
      (node (ref "U$1") (pin "9") (pinfunction "9/RX2/PWM_9") (pintype "bidirectional"))
    )
    (net (code "105") (name "RS_LCD") (class "Default")
      (node (ref "LCD_HEADER") (pin "7") (pinfunction "7_7") (pintype "passive"))
      (node (ref "U$1") (pin "10") (pinfunction "10/TX2/PWM_10") (pintype "bidirectional"))
    )
    (net (code "106") (name "SCK") (class "Default")
      (node (ref "LCD_HEADER") (pin "5") (pinfunction "5_5") (pintype "passive"))
      (node (ref "U$1") (pin "13") (pinfunction "13/SCK/LED_13") (pintype "bidirectional"))
    )
    (net (code "107") (name "SCK_B") (class "Default")
      (node (ref "IC10") (pin "7") (pinfunction "CLK_7") (pintype "bidirectional"))
      (node (ref "IC3") (pin "7") (pinfunction "SCLK_7") (pintype "bidirectional"))
      (node (ref "IC4") (pin "7") (pinfunction "CLK_7") (pintype "bidirectional"))
      (node (ref "IC5") (pin "7") (pinfunction "CLK_7") (pintype "bidirectional"))
      (node (ref "IC8") (pin "7") (pinfunction "CLK_7") (pintype "bidirectional"))
      (node (ref "U$1") (pin "1") (pinfunction "1/TX1/T_1") (pintype "bidirectional"))
    )
    (net (code "108") (name "VBAT") (class "Default")
      (node (ref "U$1") (pin "VBAT") (pinfunction "VBAT_VBAT") (pintype "power_in"))
    )
    (net (code "109") (name "VDD") (class "Default")
      (node (ref "C12") (pin "2") (pinfunction "P$2_2") (pintype "passive"))
      (node (ref "C13") (pin "2") (pinfunction "P$2_2") (pintype "passive"))
      (node (ref "C15") (pin "2") (pinfunction "P$2_2") (pintype "passive"))
      (node (ref "C20") (pin "2") (pinfunction "P$2_2") (pintype "passive"))
      (node (ref "C21") (pin "2") (pinfunction "P$2_2") (pintype "passive"))
      (node (ref "C22") (pin "2") (pinfunction "P$2_2") (pintype "passive"))
      (node (ref "C23") (pin "2") (pinfunction "P$2_2") (pintype "passive"))
      (node (ref "C24") (pin "2") (pinfunction "P$2_2") (pintype "passive"))
      (node (ref "C25") (pin "2") (pinfunction "P$2_2") (pintype "passive"))
      (node (ref "CP3") (pin "+") (pinfunction "+_+") (pintype "passive"))
      (node (ref "D1") (pin "A") (pinfunction "A_A") (pintype "bidirectional"))
      (node (ref "D2") (pin "A") (pinfunction "A_A") (pintype "bidirectional"))
      (node (ref "D3") (pin "A") (pinfunction "A_A") (pintype "bidirectional"))
      (node (ref "D4") (pin "A") (pinfunction "A_A") (pintype "bidirectional"))
      (node (ref "IC1") (pin "8") (pinfunction "V+_8") (pintype "power_in"))
      (node (ref "IC10") (pin "10") (pinfunction "PR_10") (pintype "bidirectional"))
      (node (ref "IC10") (pin "13") (pinfunction "VL_13") (pintype "power_in"))
      (node (ref "IC10") (pin "5") (pinfunction "VDD_5") (pintype "power_in"))
      (node (ref "IC10") (pin "6") (pinfunction "SHDN_6") (pintype "bidirectional"))
      (node (ref "IC2") (pin "8") (pinfunction "V+_8") (pintype "power_in"))
      (node (ref "IC4") (pin "10") (pinfunction "PR_10") (pintype "bidirectional"))
      (node (ref "IC4") (pin "13") (pinfunction "VL_13") (pintype "power_in"))
      (node (ref "IC4") (pin "5") (pinfunction "VDD_5") (pintype "power_in"))
      (node (ref "IC4") (pin "6") (pinfunction "SHDN_6") (pintype "bidirectional"))
      (node (ref "IC5") (pin "10") (pinfunction "PR_10") (pintype "bidirectional"))
      (node (ref "IC5") (pin "13") (pinfunction "VL_13") (pintype "power_in"))
      (node (ref "IC5") (pin "5") (pinfunction "VDD_5") (pintype "power_in"))
      (node (ref "IC5") (pin "6") (pinfunction "SHDN_6") (pintype "bidirectional"))
      (node (ref "IC6") (pin "1") (pinfunction "IN_1") (pintype "bidirectional"))
      (node (ref "IC7") (pin "8") (pinfunction "V+_8") (pintype "power_in"))
      (node (ref "IC8") (pin "10") (pinfunction "PR_10") (pintype "bidirectional"))
      (node (ref "IC8") (pin "13") (pinfunction "VL_13") (pintype "power_in"))
      (node (ref "IC8") (pin "5") (pinfunction "VDD_5") (pintype "power_in"))
      (node (ref "IC8") (pin "6") (pinfunction "SHDN_6") (pintype "bidirectional"))
      (node (ref "IC9") (pin "8") (pinfunction "V+_8") (pintype "power_in"))
      (node (ref "JP1") (pin "11") (pinfunction "11_11") (pintype "passive"))
      (node (ref "JP1") (pin "2") (pinfunction "2_2") (pintype "passive"))
      (node (ref "JP11") (pin "11") (pinfunction "11_11") (pintype "passive"))
      (node (ref "JP11") (pin "2") (pinfunction "2_2") (pintype "passive"))
      (node (ref "JP2") (pin "11") (pinfunction "11_11") (pintype "passive"))
      (node (ref "JP2") (pin "2") (pinfunction "2_2") (pintype "passive"))
      (node (ref "JP8") (pin "11") (pinfunction "11_11") (pintype "passive"))
      (node (ref "JP8") (pin "2") (pinfunction "2_2") (pintype "passive"))
      (node (ref "L1") (pin "2") (pinfunction "P$2_2") (pintype "passive"))
      (node (ref "L2") (pin "2") (pinfunction "P$2_2") (pintype "passive"))
      (node (ref "L4") (pin "1") (pinfunction "P$1_1") (pintype "passive"))
      (node (ref "R11") (pin "2") (pinfunction "P$2_2") (pintype "passive"))
      (node (ref "R12") (pin "2") (pinfunction "P$2_2") (pintype "passive"))
      (node (ref "R19") (pin "2") (pinfunction "P$2_2") (pintype "passive"))
      (node (ref "R28") (pin "P$2") (pinfunction "2_P$2") (pintype "passive"))
      (node (ref "R29") (pin "2") (pinfunction "P$2_2") (pintype "passive"))
      (node (ref "R32") (pin "2") (pinfunction "P$2_2") (pintype "passive"))
      (node (ref "R33") (pin "P$2") (pinfunction "2_P$2") (pintype "passive"))
      (node (ref "R34") (pin "2") (pinfunction "P$2_2") (pintype "passive"))
      (node (ref "R43") (pin "2") (pinfunction "P$2_2") (pintype "passive"))
      (node (ref "R44") (pin "2") (pinfunction "P$2_2") (pintype "passive"))
      (node (ref "R46") (pin "2") (pinfunction "P$2_2") (pintype "passive"))
      (node (ref "R47") (pin "2") (pinfunction "P$2_2") (pintype "passive"))
      (node (ref "R61") (pin "2") (pinfunction "P$2_2") (pintype "passive"))
      (node (ref "R62") (pin "2") (pinfunction "P$2_2") (pintype "passive"))
      (node (ref "R64") (pin "2") (pinfunction "P$2_2") (pintype "passive"))
      (node (ref "R65") (pin "2") (pinfunction "P$2_2") (pintype "passive"))
      (node (ref "R79") (pin "2") (pinfunction "P$2_2") (pintype "passive"))
      (node (ref "R8") (pin "2") (pinfunction "P$2_2") (pintype "passive"))
      (node (ref "R80") (pin "2") (pinfunction "P$2_2") (pintype "passive"))
      (node (ref "R82") (pin "2") (pinfunction "P$2_2") (pintype "passive"))
      (node (ref "R83") (pin "2") (pinfunction "P$2_2") (pintype "passive"))
      (node (ref "R9") (pin "2") (pinfunction "P$2_2") (pintype "passive"))
    )
    (net (code "110") (name "VMON1") (class "Default")
      (node (ref "JP1") (pin "7") (pinfunction "7_7") (pintype "passive"))
      (node (ref "R18") (pin "1") (pinfunction "P$1_1") (pintype "passive"))
      (node (ref "R26") (pin "P$2") (pinfunction "2_P$2") (pintype "passive"))
    )
    (net (code "111") (name "VMON1_B") (class "Default")
      (node (ref "C9") (pin "2") (pinfunction "P$2_2") (pintype "passive"))
      (node (ref "R26") (pin "P$1") (pinfunction "1_P$1") (pintype "passive"))
      (node (ref "R27") (pin "P$2") (pinfunction "2_P$2") (pintype "passive"))
      (node (ref "U$1") (pin "A10") (pinfunction "A10_A10") (pintype "bidirectional"))
    )
    (net (code "112") (name "VMON2") (class "Default")
      (node (ref "JP2") (pin "7") (pinfunction "7_7") (pintype "passive"))
      (node (ref "R24") (pin "P$2") (pinfunction "2_P$2") (pintype "passive"))
      (node (ref "R54") (pin "1") (pinfunction "P$1_1") (pintype "passive"))
    )
    (net (code "113") (name "VMON2_B") (class "Default")
      (node (ref "C6") (pin "2") (pinfunction "P$2_2") (pintype "passive"))
      (node (ref "R24") (pin "P$1") (pinfunction "1_P$1") (pintype "passive"))
      (node (ref "R25") (pin "P$2") (pinfunction "2_P$2") (pintype "passive"))
      (node (ref "U$1") (pin "22/A8") (pinfunction "22/A8/T/PWM_22/A8") (pintype "bidirectional"))
    )
    (net (code "114") (name "VMON3") (class "Default")
      (node (ref "JP8") (pin "7") (pinfunction "7_7") (pintype "passive"))
      (node (ref "R22") (pin "P$2") (pinfunction "2_P$2") (pintype "passive"))
      (node (ref "R72") (pin "1") (pinfunction "P$1_1") (pintype "passive"))
    )
    (net (code "115") (name "VMON3_B") (class "Default")
      (node (ref "C4") (pin "2") (pinfunction "P$2_2") (pintype "passive"))
      (node (ref "R22") (pin "P$1") (pinfunction "1_P$1") (pintype "passive"))
      (node (ref "R23") (pin "P$2") (pinfunction "2_P$2") (pintype "passive"))
      (node (ref "U$1") (pin "20/A6") (pinfunction "20/A6/PWM_20/A6") (pintype "bidirectional"))
    )
    (net (code "116") (name "VMON4") (class "Default")
      (node (ref "JP11") (pin "7") (pinfunction "7_7") (pintype "passive"))
      (node (ref "R20") (pin "P$2") (pinfunction "2_P$2") (pintype "passive"))
      (node (ref "R90") (pin "1") (pinfunction "P$1_1") (pintype "passive"))
    )
    (net (code "117") (name "VMON4_B") (class "Default")
      (node (ref "C3") (pin "2") (pinfunction "P$2_2") (pintype "passive"))
      (node (ref "R20") (pin "P$1") (pinfunction "1_P$1") (pintype "passive"))
      (node (ref "R21") (pin "P$2") (pinfunction "2_P$2") (pintype "passive"))
      (node (ref "U$1") (pin "18/A4") (pinfunction "18/A4/T/SDA0_18/A4") (pintype "bidirectional"))
    )
    (net (code "118") (name "VSET1") (class "Default")
      (node (ref "IC1") (pin "3") (pinfunction "+IN_3") (pintype "input"))
      (node (ref "IC1") (pin "6") (pinfunction "-IN_6") (pintype "input"))
      (node (ref "IC3") (pin "1") (pinfunction "VOUTA_1") (pintype "output"))
      (node (ref "JP1") (pin "10") (pinfunction "10_10") (pintype "passive"))
      (node (ref "TP8") (pin "P$1") (pinfunction "P$1_P$1") (pintype "bidirectional"))
    )
    (net (code "119") (name "VSET2") (class "Default")
      (node (ref "IC2") (pin "3") (pinfunction "+IN_3") (pintype "input"))
      (node (ref "IC2") (pin "6") (pinfunction "-IN_6") (pintype "input"))
      (node (ref "IC3") (pin "2") (pinfunction "VOUTB_2") (pintype "output"))
      (node (ref "JP2") (pin "10") (pinfunction "10_10") (pintype "passive"))
      (node (ref "TP14") (pin "P$1") (pinfunction "P$1_P$1") (pintype "bidirectional"))
    )
    (net (code "120") (name "VSET3") (class "Default")
      (node (ref "IC3") (pin "4") (pinfunction "VOUTC_4") (pintype "output"))
      (node (ref "IC7") (pin "3") (pinfunction "+IN_3") (pintype "input"))
      (node (ref "IC7") (pin "6") (pinfunction "-IN_6") (pintype "input"))
      (node (ref "JP8") (pin "10") (pinfunction "10_10") (pintype "passive"))
      (node (ref "TP20") (pin "P$1") (pinfunction "P$1_P$1") (pintype "bidirectional"))
    )
    (net (code "121") (name "VSET4") (class "Default")
      (node (ref "IC3") (pin "5") (pinfunction "VOUTD_5") (pintype "output"))
      (node (ref "IC9") (pin "3") (pinfunction "+IN_3") (pintype "input"))
      (node (ref "IC9") (pin "6") (pinfunction "-IN_6") (pintype "input"))
      (node (ref "JP11") (pin "10") (pinfunction "10_10") (pintype "passive"))
      (node (ref "TP26") (pin "P$1") (pinfunction "P$1_P$1") (pintype "bidirectional"))
    )
    (net (code "122") (name "VUSB") (class "Default")
      (node (ref "U$1") (pin "VUSB") (pinfunction "VUSB_VUSB") (pintype "power_in"))
    )
    (net (code "123") (name "unconnected-(IC4-SDO-Pad1)") (class "Default")
      (node (ref "IC4") (pin "1") (pinfunction "SDO_1") (pintype "bidirectional"))
    )
    (net (code "124") (name "unconnected-(IC5-SDO-Pad1)") (class "Default")
      (node (ref "IC5") (pin "1") (pinfunction "SDO_1") (pintype "bidirectional"))
    )
    (net (code "125") (name "unconnected-(IC8-SDO-Pad1)") (class "Default")
      (node (ref "IC8") (pin "1") (pinfunction "SDO_1") (pintype "bidirectional"))
    )
    (net (code "126") (name "unconnected-(IC10-SDO-Pad1)") (class "Default")
      (node (ref "IC10") (pin "1") (pinfunction "SDO_1") (pintype "bidirectional"))
    )
    (net (code "127") (name "unconnected-(S1-1-PadP$1)") (class "Default")
      (node (ref "S1") (pin "P$1") (pinfunction "1_P$1") (pintype "bidirectional"))
    )
    (net (code "128") (name "unconnected-(S2-1-PadP$1)") (class "Default")
      (node (ref "S2") (pin "P$1") (pinfunction "1_P$1") (pintype "bidirectional"))
    )
    (net (code "129") (name "unconnected-(S3-1-PadP$1)") (class "Default")
      (node (ref "S3") (pin "P$1") (pinfunction "1_P$1") (pintype "bidirectional"))
    )
    (net (code "130") (name "unconnected-(S4-1-PadP$1)") (class "Default")
      (node (ref "S4") (pin "P$1") (pinfunction "1_P$1") (pintype "bidirectional"))
    )
    (net (code "131") (name "unconnected-(U$1-PadPGM)") (class "Default")
      (node (ref "U$1") (pin "PGM") (pinfunction "PGM_PGM") (pintype "bidirectional"))
    )
  )
)
